# citizen_science_flora.net
KiCad netlist of a schematic drawn in EAGLE
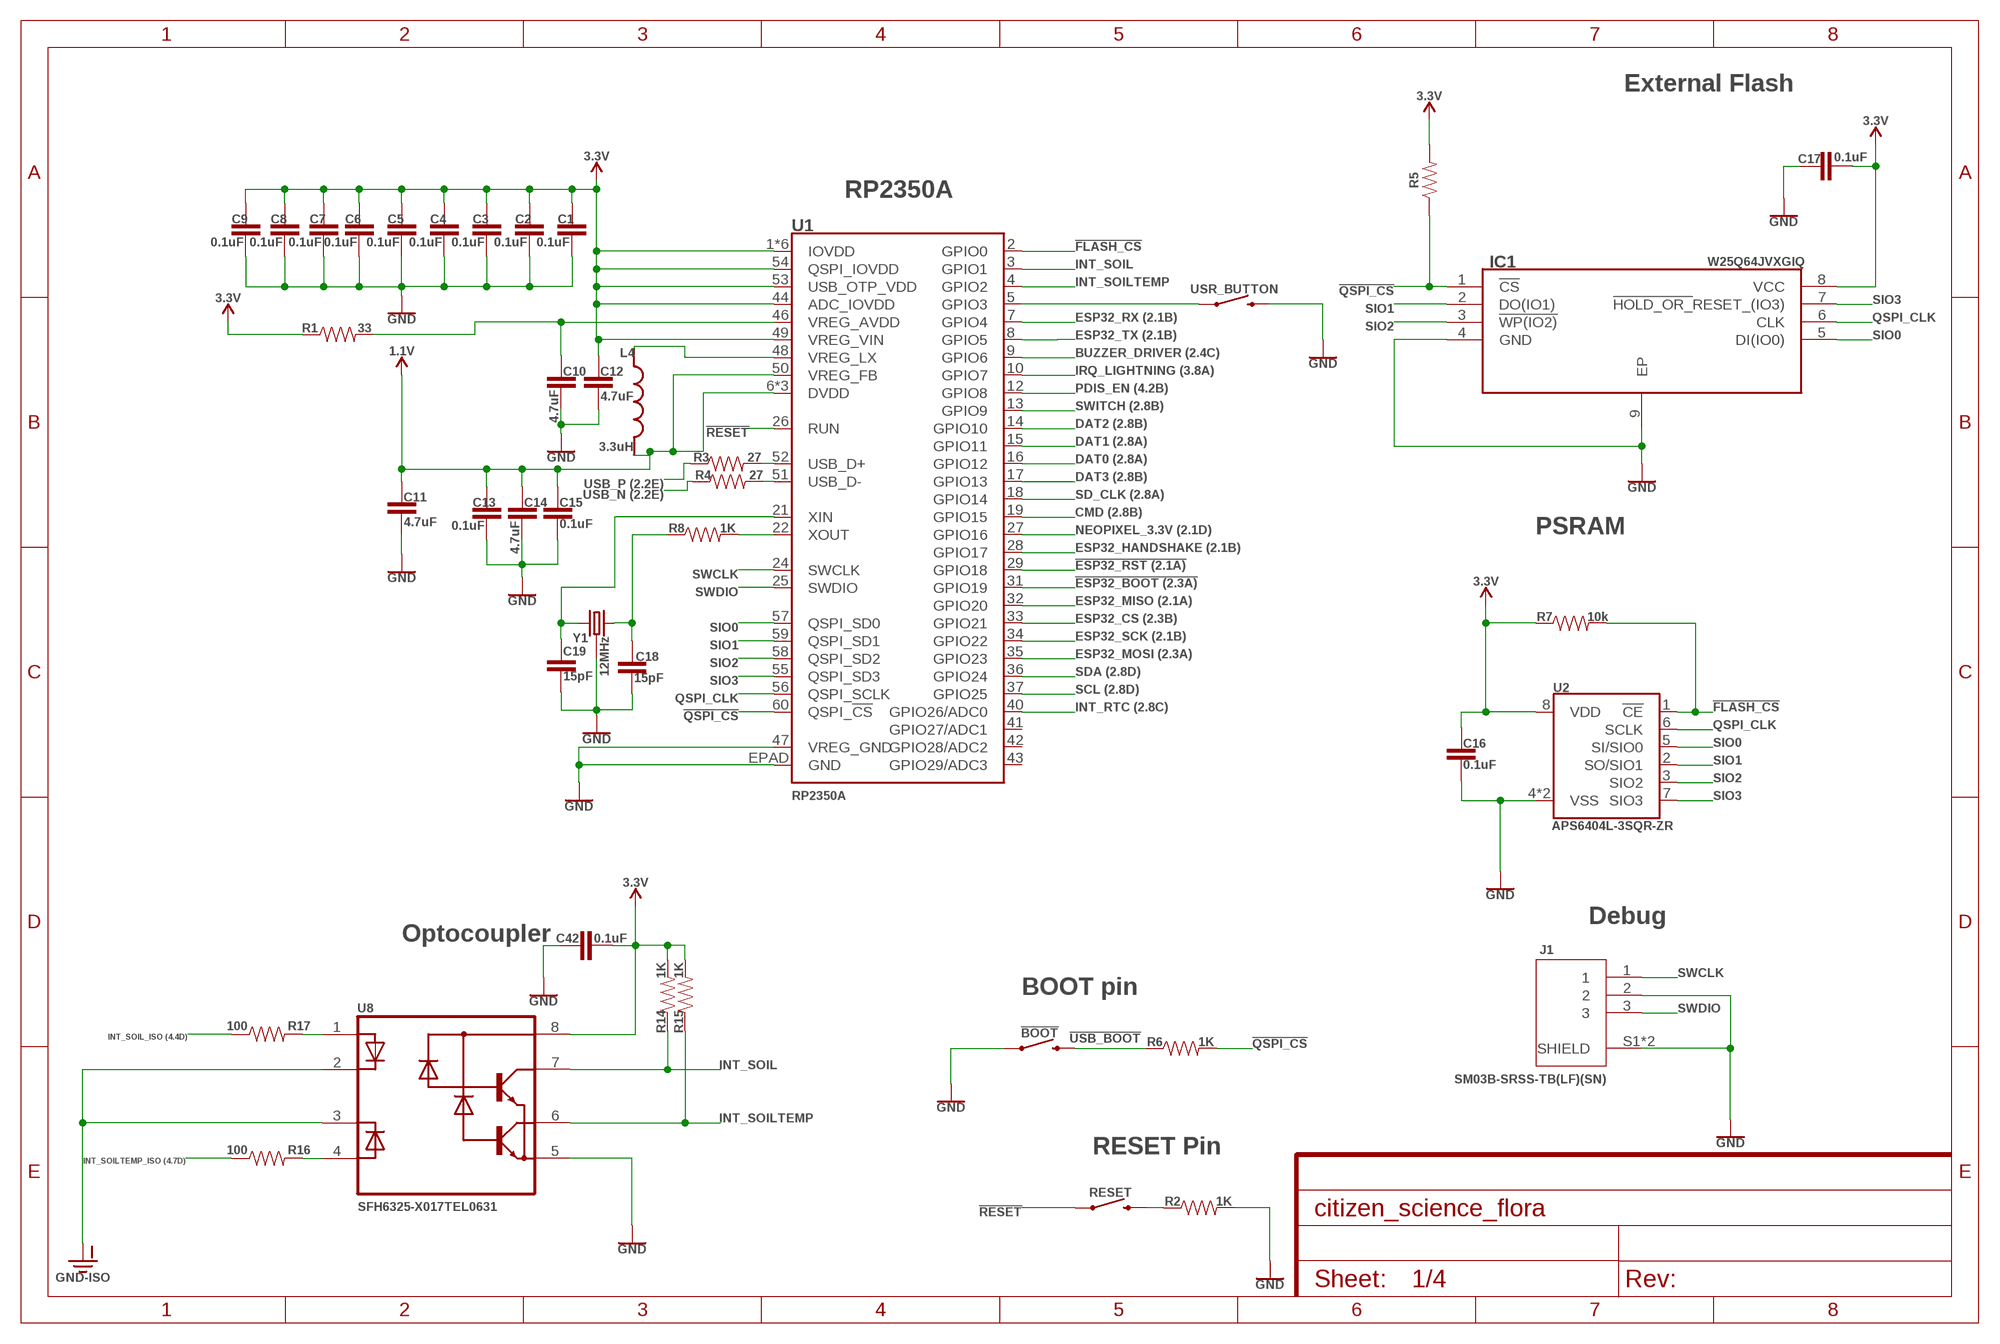
[diagram p0: schematic, sheet 1]
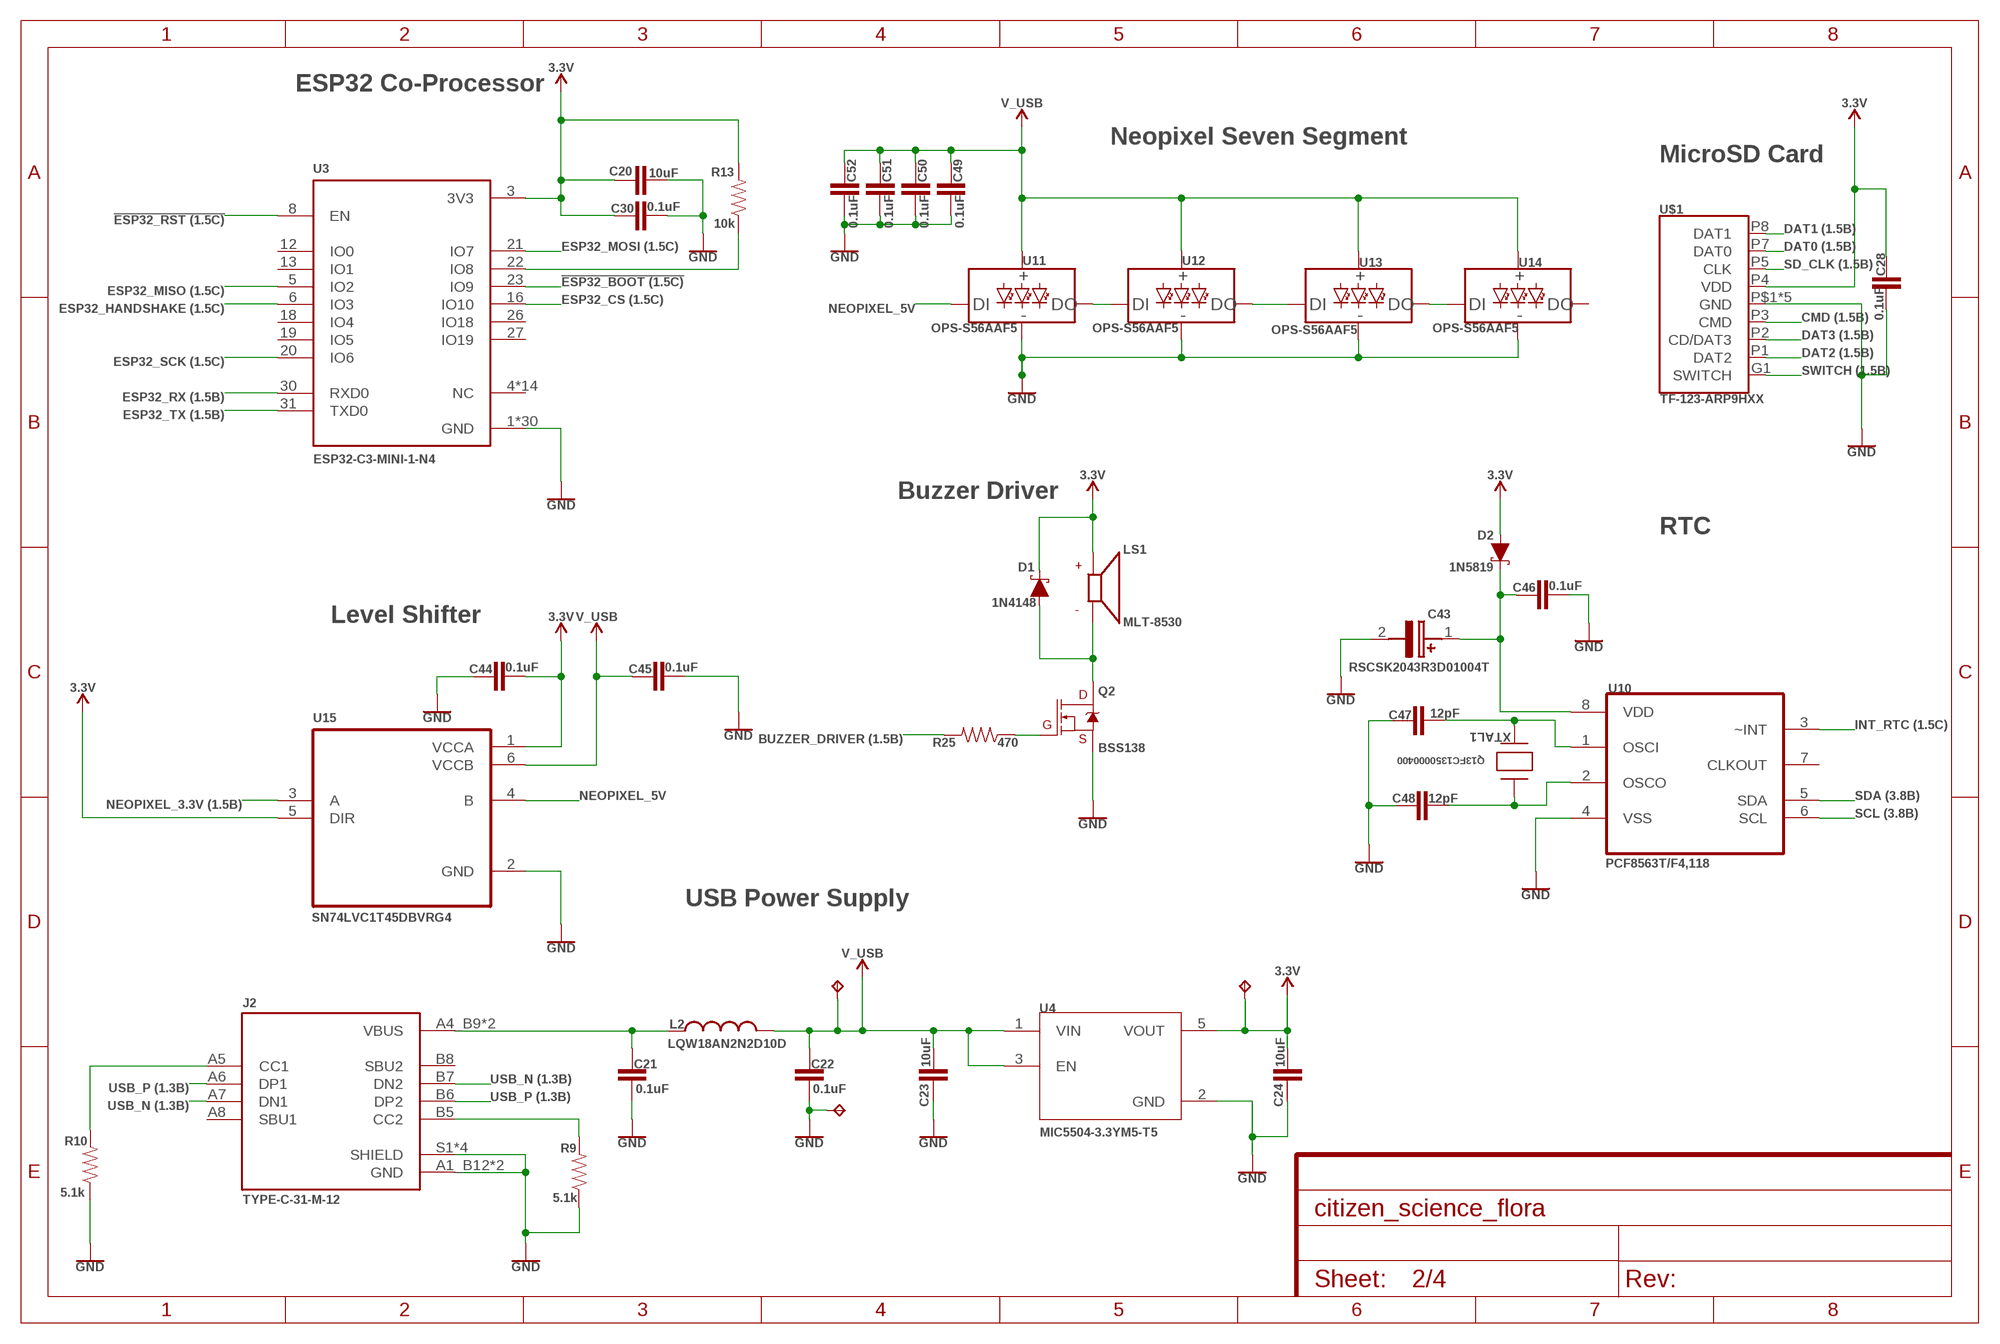
[diagram p1: schematic, sheet 2]
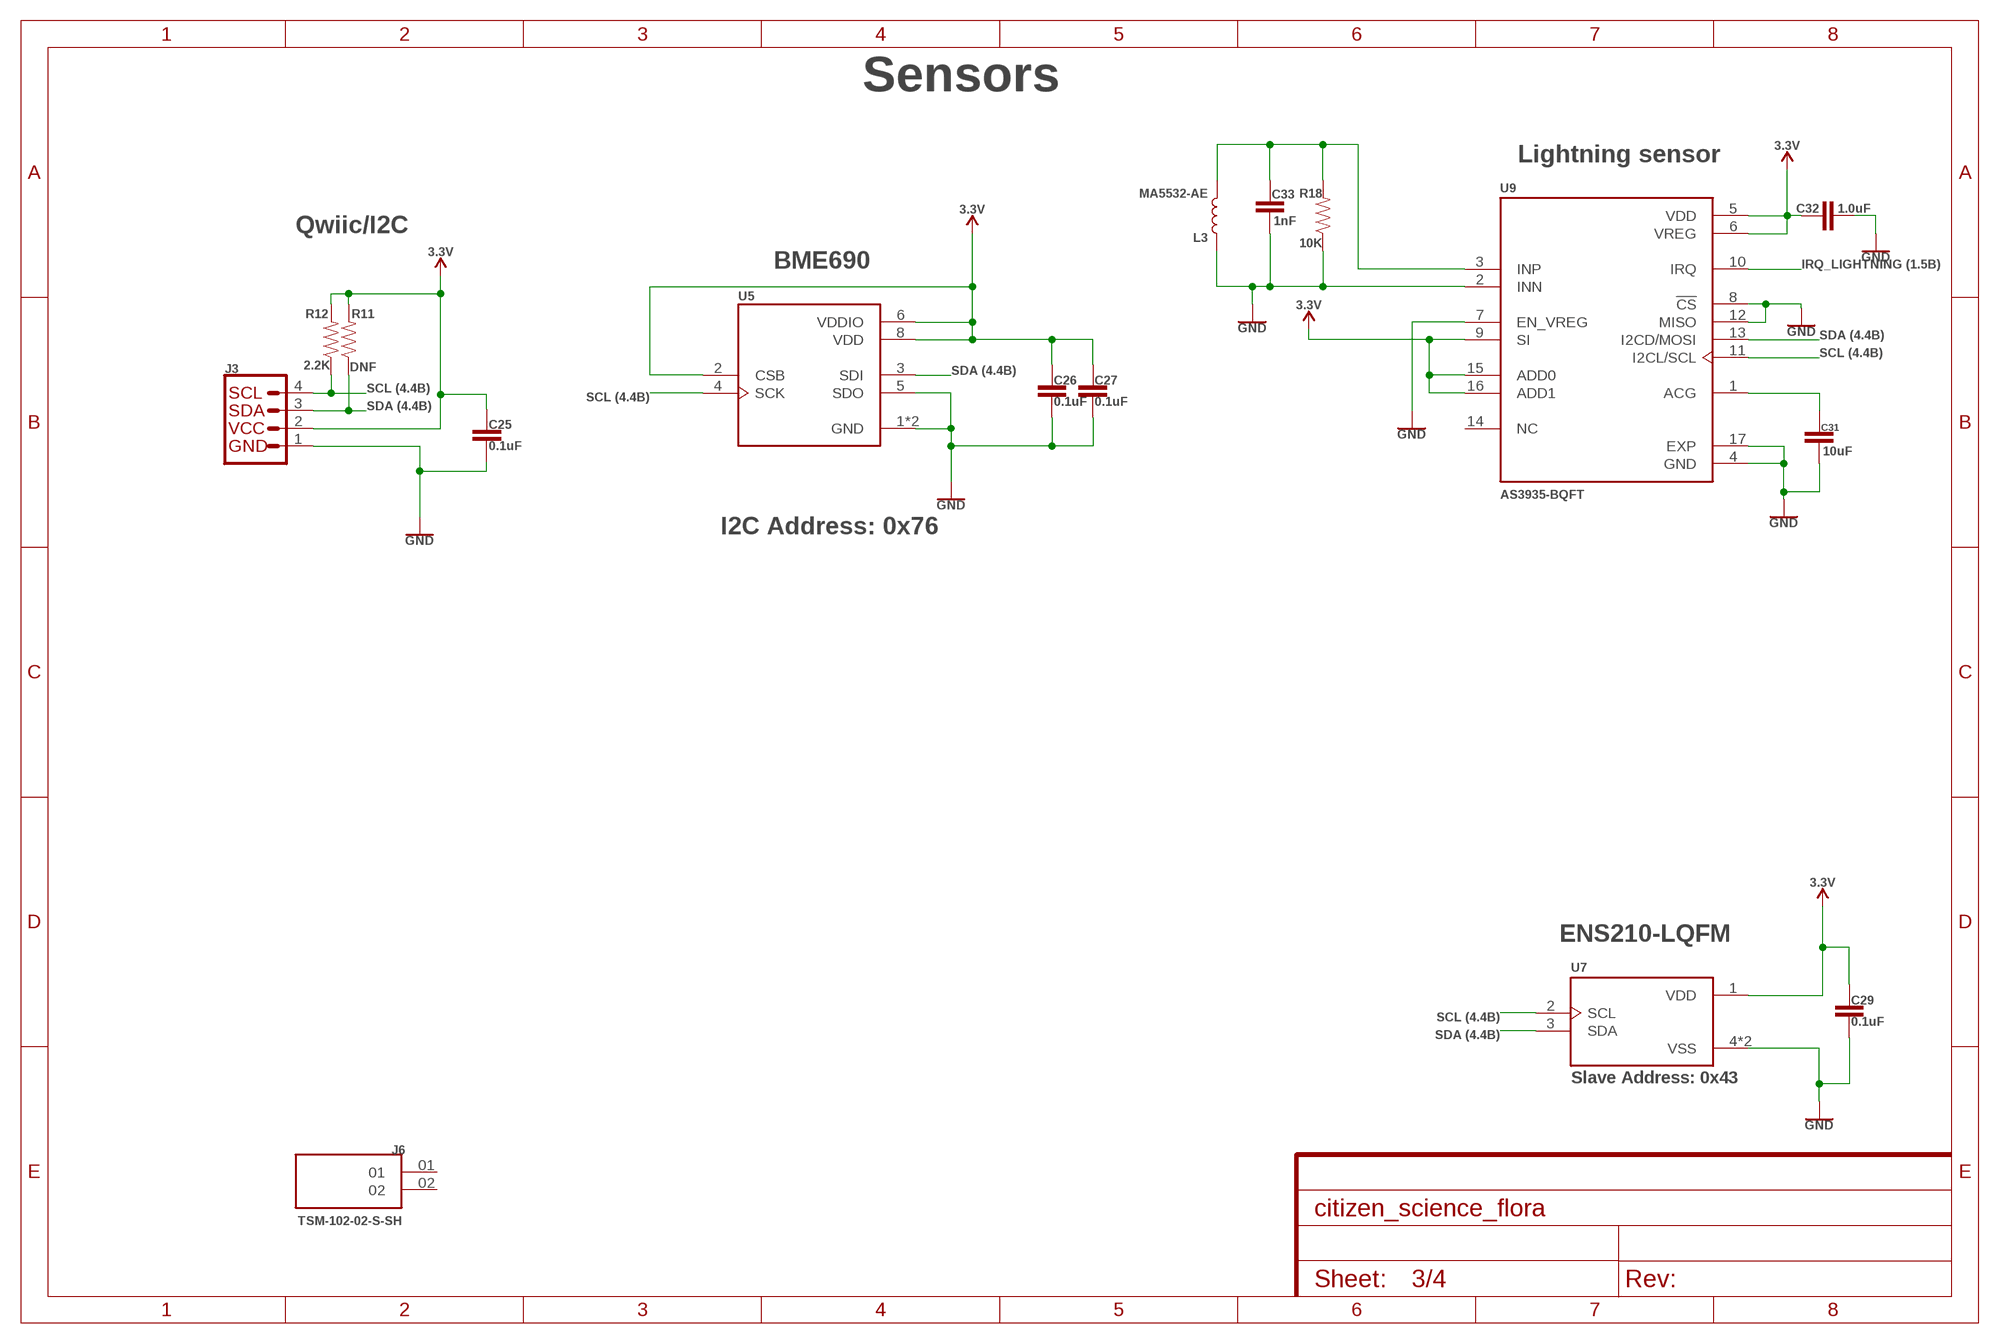
[diagram p2: schematic, sheet 3]
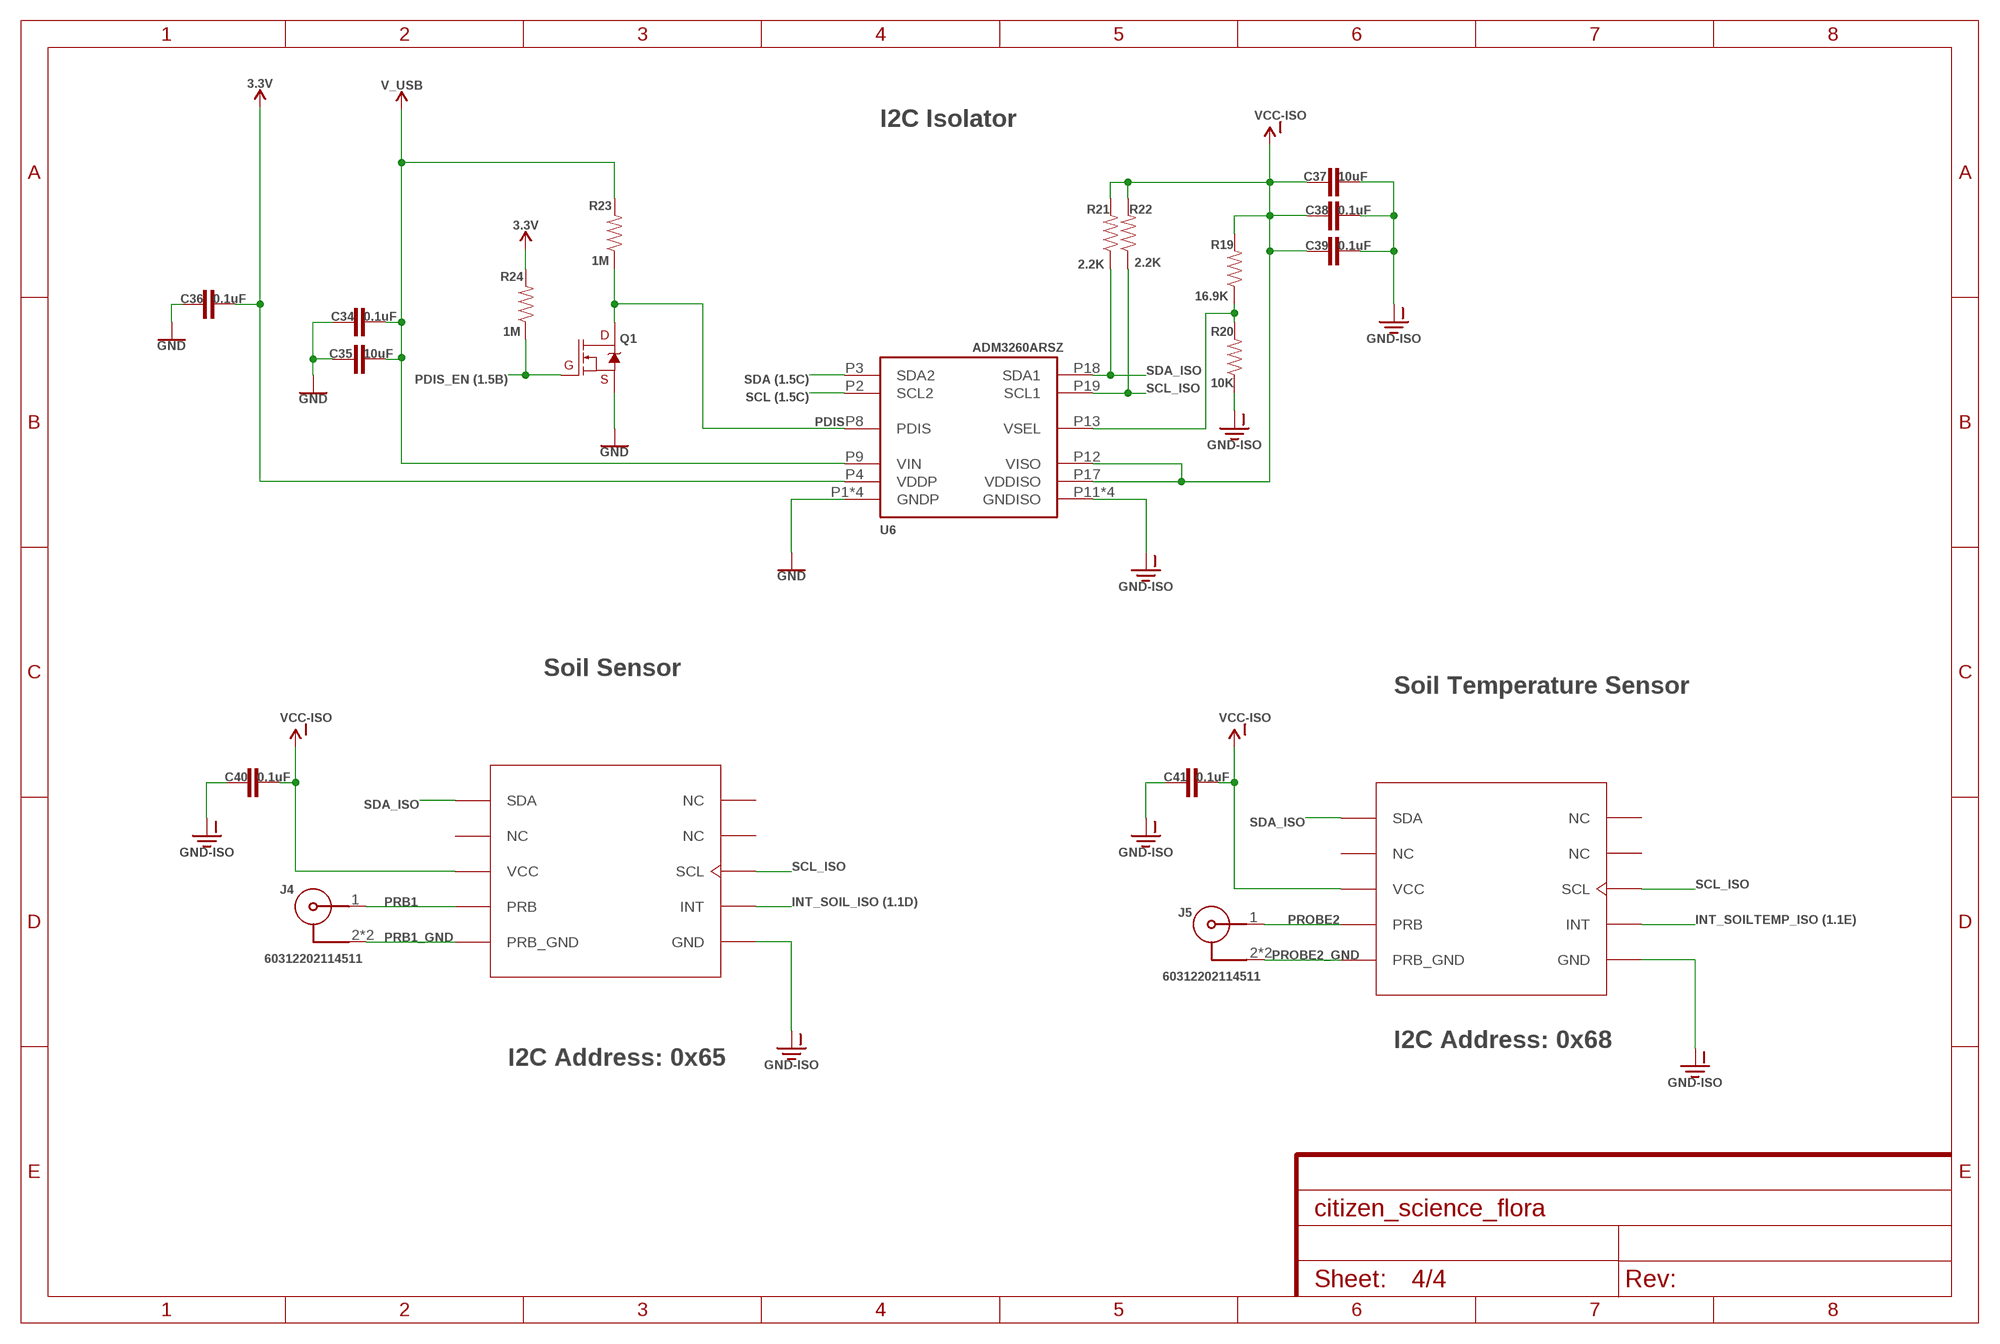
[diagram p3: schematic, sheet 4]

(export (version "E")
  (design (tool "Eeschema 10.0.6"))
  (components
    (comp (ref "3.3V")
      (value "TPB1,27")
      (footprint "eagle-import:B1,27")
      (libsource (lib "eagle-import") (part "TPB1,27"))
    )
    (comp (ref "C20")
      (value "10uF")
      (footprint "eagle-import:0402-TIGHT")
      (libsource (lib "eagle-import") (part "10UF-0402T-6.3V-20%"))
    )
    (comp (ref "C21")
      (value "0.1uF")
      (footprint "eagle-import:0402")
      (libsource (lib "eagle-import") (part "0.1UF-0402-6.3V-10%-X7R"))
    )
    (comp (ref "C22")
      (value "0.1uF")
      (footprint "eagle-import:0402")
      (libsource (lib "eagle-import") (part "0.1UF-0402-6.3V-10%-X7R"))
    )
    (comp (ref "C23")
      (value "10uF")
      (footprint "eagle-import:0402-TIGHT")
      (libsource (lib "eagle-import") (part "10UF-0402T-6.3V-20%"))
    )
    (comp (ref "C24")
      (value "10uF")
      (footprint "eagle-import:0402-TIGHT")
      (libsource (lib "eagle-import") (part "10UF-0402T-6.3V-20%"))
    )
    (comp (ref "C28")
      (value "0.1uF")
      (footprint "eagle-import:0402-TIGHT")
      (libsource (lib "eagle-import") (part "0.1UF-0402T-16V-10%-X7R-WE"))
    )
    (comp (ref "C30")
      (value "0.1uF")
      (footprint "eagle-import:0402")
      (libsource (lib "eagle-import") (part "0.1UF-0402-6.3V-10%-X7R"))
    )
    (comp (ref "C43")
      (value "RSCSK2043R3D01004T")
      (footprint "eagle-import:RSCSK2043R3D01004T")
      (fields (field (name "MOUSER_PART_NUMBER") "555-DSK3R3H204T614H2"))
      (libsource (lib "eagle-import") (part "RSCSK2043R3D01004T"))
    )
    (comp (ref "C44")
      (value "0.1uF")
      (footprint "eagle-import:0402")
      (libsource (lib "eagle-import") (part "0.1UF-0402-6.3V-10%-X7R"))
    )
    (comp (ref "C45")
      (value "0.1uF")
      (footprint "eagle-import:0402")
      (libsource (lib "eagle-import") (part "0.1UF-0402-6.3V-10%-X7R"))
    )
    (comp (ref "C46")
      (value "0.1uF")
      (footprint "eagle-import:0402")
      (libsource (lib "eagle-import") (part "0.1UF-0402-6.3V-10%-X7R"))
    )
    (comp (ref "C47")
      (value "12pF")
      (footprint "eagle-import:0402")
      (libsource (lib "eagle-import") (part "12PF-0402-50V-5%"))
    )
    (comp (ref "C48")
      (value "12pF")
      (footprint "eagle-import:0402")
      (libsource (lib "eagle-import") (part "12PF-0402-50V-5%"))
    )
    (comp (ref "C49")
      (value "0.1uF")
      (footprint "eagle-import:0402")
      (libsource (lib "eagle-import") (part "0.1UF-0402-6.3V-10%-X7R"))
    )
    (comp (ref "C50")
      (value "0.1uF")
      (footprint "eagle-import:0402")
      (libsource (lib "eagle-import") (part "0.1UF-0402-6.3V-10%-X7R"))
    )
    (comp (ref "C51")
      (value "0.1uF")
      (footprint "eagle-import:0402")
      (libsource (lib "eagle-import") (part "0.1UF-0402-6.3V-10%-X7R"))
    )
    (comp (ref "C52")
      (value "0.1uF")
      (footprint "eagle-import:0402")
      (libsource (lib "eagle-import") (part "0.1UF-0402-6.3V-10%-X7R"))
    )
    (comp (ref "D1")
      (value "1N4148")
      (footprint "eagle-import:SOD-323")
      (libsource (lib "eagle-import") (part "DIODE-SCHOTTKY-BAT60A"))
    )
    (comp (ref "D2")
      (value "1N5819")
      (footprint "eagle-import:SOD-323")
      (libsource (lib "eagle-import") (part "DIODE-SCHOTTKY-BAT20J"))
    )
    (comp (ref "GND")
      (value "TPB1,27")
      (footprint "eagle-import:B1,27")
      (libsource (lib "eagle-import") (part "TPB1,27"))
    )
    (comp (ref "J2")
      (value "TYPE-C-31-M-12")
      (footprint "eagle-import:HRO_TYPE-C-31-M-12")
      (fields (field (name "MF") "HRO Electronics Co., Ltd."))
      (libsource (lib "eagle-import") (part "TYPE-C-31-M-12"))
    )
    (comp (ref "L2")
      (value "LQW18AN2N2D10D")
      (footprint "eagle-import:INDC1608X100N")
      (fields (field (name "MF") "Murata"))
      (libsource (lib "eagle-import") (part "LQW18AN2N2D10D"))
    )
    (comp (ref "LS1")
      (value "MLT-8530")
      (footprint "eagle-import:XDCR_CMT-8504-100-SMT-TR")
      (fields (field (name "MANUFACTURER") "CUI Inc."))
      (libsource (lib "eagle-import") (part "CMT-8504-100-SMT-TR"))
    )
    (comp (ref "Q2")
      (value "BSS138")
      (footprint "eagle-import:SOT323")
      (libsource (lib "eagle-import") (part "MOSFET-NCH-2N7002PW"))
    )
    (comp (ref "R9")
      (value "5.1k")
      (footprint "eagle-import:0402")
      (libsource (lib "eagle-import") (part "5.1KOHM-0402-1/16W-1%"))
    )
    (comp (ref "R10")
      (value "5.1k")
      (footprint "eagle-import:0402")
      (libsource (lib "eagle-import") (part "5.1KOHM-0402-1/16W-1%"))
    )
    (comp (ref "R13")
      (value "10k")
      (footprint "eagle-import:0402")
      (libsource (lib "eagle-import") (part "10KOHM-0402-1/16W-1%"))
    )
    (comp (ref "R25")
      (value "470")
      (footprint "eagle-import:0402")
      (libsource (lib "eagle-import") (part "10KOHM-0402-1/16W-1%"))
    )
    (comp (ref "U$1")
      (value "TF-123-ARP9HXX")
      (footprint "eagle-import:MICROSDCARD")
      (libsource (lib "eagle-import") (part "TF-123-ARP9HXX"))
    )
    (comp (ref "U3")
      (value "ESP32-C3-MINI-1-N4")
      (footprint "eagle-import:XCVR_ESP32-C3-MINI-1-N4")
      (fields (field (name "MF") "Espressif Systems"))
      (libsource (lib "eagle-import") (part "ESP32-C3-MINI-1-N4"))
    )
    (comp (ref "U4")
      (value "MIC5504-3.3YM5-T5")
      (footprint "eagle-import:SOT95P280X145-5N")
      (fields (field (name "MF") "Microchip"))
      (libsource (lib "eagle-import") (part "MIC5504-3.3YM5-T5"))
    )
    (comp (ref "U10")
      (value "PCF8563T/F4,118")
      (footprint "eagle-import:SOIC127P600X175-8N")
      (fields (field (name "MF") "NXP USA"))
      (libsource (lib "eagle-import") (part "PCF8563T/F4,118"))
    )
    (comp (ref "U11")
      (value "OPS-S56AAF5")
      (footprint "eagle-import:OPS-S56AAF5")
      (libsource (lib "eagle-import") (part "OPS-S56AAF5"))
    )
    (comp (ref "U12")
      (value "OPS-S56AAF5")
      (footprint "eagle-import:OPS-S56AAF5")
      (libsource (lib "eagle-import") (part "OPS-S56AAF5"))
    )
    (comp (ref "U13")
      (value "OPS-S56AAF5")
      (footprint "eagle-import:OPS-S56AAF5")
      (libsource (lib "eagle-import") (part "OPS-S56AAF5"))
    )
    (comp (ref "U14")
      (value "OPS-S56AAF5")
      (footprint "eagle-import:OPS-S56AAF5")
      (libsource (lib "eagle-import") (part "OPS-S56AAF5"))
    )
    (comp (ref "U15")
      (value "SN74LVC1T45DBVRG4")
      (footprint "eagle-import:SOT95P280X145-6N")
      (fields (field (name "MF") "Texas Instruments"))
      (libsource (lib "eagle-import") (part "SN74LVC1T45DBVRG4"))
    )
    (comp (ref "USB")
      (value "V_USB")
      (footprint "eagle-import:B1,27")
      (libsource (lib "eagle-import") (part "TPB1,27"))
    )
    (comp (ref "XTAL1")
      (value "Q13FC1350000400")
      (footprint "eagle-import:XTAL_FC-135_EPS")
      (fields (field (name "MF") "EPSON"))
      (libsource (lib "eagle-import") (part "Q13FC1350000400"))
    )
    (comp (ref "C25")
      (value "0.1uF")
      (footprint "eagle-import:0402-TIGHT")
      (libsource (lib "eagle-import") (part "0.1UF-0402T-16V-10%-X7R-WE"))
    )
    (comp (ref "C26")
      (value "0.1uF")
      (footprint "eagle-import:0402-TIGHT")
      (libsource (lib "eagle-import") (part "0.1UF-0402T-16V-10%-X7R-WE"))
    )
    (comp (ref "C27")
      (value "0.1uF")
      (footprint "eagle-import:0402-TIGHT")
      (libsource (lib "eagle-import") (part "0.1UF-0402T-16V-10%-X7R-WE"))
    )
    (comp (ref "C29")
      (value "0.1uF")
      (footprint "eagle-import:0402-TIGHT")
      (libsource (lib "eagle-import") (part "0.1UF-0402T-16V-10%-X7R-WE"))
    )
    (comp (ref "C31")
      (value "10uF")
      (footprint "eagle-import:0402-TIGHT")
      (libsource (lib "eagle-import") (part "10UF-0402T-6.3V-20%"))
    )
    (comp (ref "C32")
      (value "1.0uF")
      (footprint "eagle-import:0402")
      (libsource (lib "eagle-import") (part "1.0UF-0402-16V-10%"))
    )
    (comp (ref "C33")
      (value "1nF")
      (footprint "eagle-import:0402")
      (libsource (lib "eagle-import") (part "1.0NF/1000PF-0402-25V-10%-X7R"))
    )
    (comp (ref "J3")
      (value "QWIIC_CONNECTORJS-1MM")
      (footprint "eagle-import:1X04_1MM_RA")
      (libsource (lib "eagle-import") (part "QWIIC_CONNECTORJS-1MM"))
    )
    (comp (ref "J6")
      (value "TSM-102-02-S-SH")
      (footprint "eagle-import:SAMTEC_TSM-102-02-S-SH")
      (fields (field (name "MF") "Samtec"))
      (libsource (lib "eagle-import") (part "TSM-102-02-S-SH"))
    )
    (comp (ref "L3")
      (value "MA5532-AE")
      (footprint "eagle-import:MA5532-AE")
      (fields (field (name "MF") "Coilcraft"))
      (libsource (lib "eagle-import") (part "MA5532-AE"))
    )
    (comp (ref "R11")
      (value "DNF")
      (footprint "eagle-import:0402")
      (libsource (lib "eagle-import") (part "2.2KOHM-0402-1/16W-1%"))
    )
    (comp (ref "R12")
      (value "2.2K")
      (footprint "eagle-import:0402")
      (libsource (lib "eagle-import") (part "2.2KOHM-0402-1/16W-1%"))
    )
    (comp (ref "R18")
      (value "10K")
      (footprint "eagle-import:0402-TIGHT")
      (libsource (lib "eagle-import") (part "10KOHM-0402-1/10W-0.1%"))
    )
    (comp (ref "U5")
      (value "BME690")
      (footprint "eagle-import:IC_BME688")
      (fields (field (name "MF") "Bosch Sensortec") (field (name "MP") "BME688"))
      (libsource (lib "eagle-import") (part "BME690"))
    )
    (comp (ref "U7")
      (value "ENS210-LQFM")
      (footprint "eagle-import:XDCR_ENS210-LQFM")
      (fields (field (name "MF") "ScioSense"))
      (libsource (lib "eagle-import") (part "ENS210-LQFM"))
    )
    (comp (ref "U9")
      (value "AS3935-BQFT")
      (footprint "eagle-import:QFN65P400X400X80-17N")
      (fields (field (name "MF") "ScioSense"))
      (libsource (lib "eagle-import") (part "AS3935-BQFT"))
    )
    (comp (ref "C34")
      (value "0.1uF")
      (footprint "eagle-import:0402-TIGHT")
      (libsource (lib "eagle-import") (part "0.1UF-0402T-16V-10%-X7R-WE"))
    )
    (comp (ref "C35")
      (value "10uF")
      (footprint "eagle-import:0402-TIGHT")
      (libsource (lib "eagle-import") (part "10UF-0402T-6.3V-20%"))
    )
    (comp (ref "C36")
      (value "0.1uF")
      (footprint "eagle-import:0402-TIGHT")
      (libsource (lib "eagle-import") (part "0.1UF-0402T-16V-10%-X7R-WE"))
    )
    (comp (ref "C37")
      (value "10uF")
      (footprint "eagle-import:0402-TIGHT")
      (libsource (lib "eagle-import") (part "10UF-0402T-6.3V-20%"))
    )
    (comp (ref "C38")
      (value "0.1uF")
      (footprint "eagle-import:0402-TIGHT")
      (libsource (lib "eagle-import") (part "0.1UF-0402T-16V-10%-X7R-WE"))
    )
    (comp (ref "C39")
      (value "0.1uF")
      (footprint "eagle-import:0402-TIGHT")
      (libsource (lib "eagle-import") (part "0.1UF-0402T-16V-10%-X7R-WE"))
    )
    (comp (ref "C40")
      (value "0.1uF")
      (footprint "eagle-import:0402-TIGHT")
      (libsource (lib "eagle-import") (part "0.1UF-0402T-16V-10%-X7R-WE"))
    )
    (comp (ref "C41")
      (value "0.1uF")
      (footprint "eagle-import:0402-TIGHT")
      (libsource (lib "eagle-import") (part "0.1UF-0402T-16V-10%-X7R-WE"))
    )
    (comp (ref "J4")
      (value "60312202114511")
      (footprint "eagle-import:60312202114511")
      (fields (field (name "MF") "Wurth Electronics"))
      (libsource (lib "eagle-import") (part "60312202114511"))
    )
    (comp (ref "J5")
      (value "60312202114511")
      (footprint "eagle-import:60312202114511")
      (fields (field (name "MF") "Wurth Electronics"))
      (libsource (lib "eagle-import") (part "60312202114511"))
    )
    (comp (ref "Q1")
      (value "220mA/50V/3.5Ω")
      (footprint "eagle-import:SOT23-3")
      (libsource (lib "eagle-import") (part "MOSFET-NCH-BSS138"))
    )
    (comp (ref "R19")
      (value "16.9K")
      (footprint "eagle-import:0402")
      (libsource (lib "eagle-import") (part "RESISTOR0402"))
    )
    (comp (ref "R20")
      (value "10K")
      (footprint "eagle-import:0402-TIGHT")
      (libsource (lib "eagle-import") (part "10KOHM-0402-1/10W-0.1%"))
    )
    (comp (ref "R21")
      (value "2.2K")
      (footprint "eagle-import:0402")
      (libsource (lib "eagle-import") (part "2.2KOHM-0402-1/16W-1%"))
    )
    (comp (ref "R22")
      (value "2.2K")
      (footprint "eagle-import:0402")
      (libsource (lib "eagle-import") (part "2.2KOHM-0402-1/16W-1%"))
    )
    (comp (ref "R23")
      (value "1M")
      (footprint "eagle-import:0402")
      (libsource (lib "eagle-import") (part "1MOHM-0402-1/16W-5%"))
    )
    (comp (ref "R24")
      (value "1M")
      (footprint "eagle-import:0402")
      (libsource (lib "eagle-import") (part "1MOHM-0402-1/16W-5%"))
    )
    (comp (ref "U$2")
      (value "PH-OEM")
      (footprint "eagle-import:PH_SENSOR")
      (libsource (lib "eagle-import") (part "PH-OEM"))
    )
    (comp (ref "U$3")
      (value "PH-OEM")
      (footprint "eagle-import:PH_SENSOR")
      (libsource (lib "eagle-import") (part "PH-OEM"))
    )
    (comp (ref "U6")
      (value "ADM3260ARSZ")
      (footprint "eagle-import:SSOP20")
      (fields (field (name "MF") "Analog Devices"))
      (libsource (lib "eagle-import") (part "ADM3260ARSZ"))
    )
    (comp (ref "!BOOT")
      (value "MOMENTARY-SWITCH-SPST-SMD-4.6X2.8MM")
      (footprint "eagle-import:TACTILE_SWITCH_SMD_4.6X2.8MM")
      (libsource (lib "eagle-import") (part "MOMENTARY-SWITCH-SPST-SMD-4.6X2.8MM"))
    )
    (comp (ref "C1")
      (value "0.1uF")
      (footprint "eagle-import:0402-TIGHT")
      (libsource (lib "eagle-import") (part "0.1UF-0402T-16V-10%-X7R-WE"))
    )
    (comp (ref "C2")
      (value "0.1uF")
      (footprint "eagle-import:0402-TIGHT")
      (libsource (lib "eagle-import") (part "0.1UF-0402T-16V-10%-X7R-WE"))
    )
    (comp (ref "C3")
      (value "0.1uF")
      (footprint "eagle-import:0402-TIGHT")
      (libsource (lib "eagle-import") (part "0.1UF-0402T-16V-10%-X7R-WE"))
    )
    (comp (ref "C4")
      (value "0.1uF")
      (footprint "eagle-import:0402-TIGHT")
      (libsource (lib "eagle-import") (part "0.1UF-0402T-16V-10%-X7R-WE"))
    )
    (comp (ref "C5")
      (value "0.1uF")
      (footprint "eagle-import:0402-TIGHT")
      (libsource (lib "eagle-import") (part "0.1UF-0402T-16V-10%-X7R-WE"))
    )
    (comp (ref "C6")
      (value "0.1uF")
      (footprint "eagle-import:0402-TIGHT")
      (libsource (lib "eagle-import") (part "0.1UF-0402T-16V-10%-X7R-WE"))
    )
    (comp (ref "C7")
      (value "0.1uF")
      (footprint "eagle-import:0402-TIGHT")
      (libsource (lib "eagle-import") (part "0.1UF-0402T-16V-10%-X7R-WE"))
    )
    (comp (ref "C8")
      (value "0.1uF")
      (footprint "eagle-import:0402-TIGHT")
      (libsource (lib "eagle-import") (part "0.1UF-0402T-16V-10%-X7R-WE"))
    )
    (comp (ref "C9")
      (value "0.1uF")
      (footprint "eagle-import:0402-TIGHT")
      (libsource (lib "eagle-import") (part "0.1UF-0402T-16V-10%-X7R-WE"))
    )
    (comp (ref "C10")
      (value "4.7uF")
      (footprint "eagle-import:0402-TIGHT")
      (libsource (lib "eagle-import") (part "4.7UF-0402_TIGHT-6.3V-20%-X5R"))
    )
    (comp (ref "C11")
      (value "4.7uF")
      (footprint "eagle-import:0402-TIGHT")
      (libsource (lib "eagle-import") (part "4.7UF-0402_TIGHT-6.3V-20%-X5R"))
    )
    (comp (ref "C12")
      (value "4.7uF")
      (footprint "eagle-import:0402-TIGHT")
      (libsource (lib "eagle-import") (part "4.7UF-0402_TIGHT-6.3V-20%-X5R"))
    )
    (comp (ref "C13")
      (value "0.1uF")
      (footprint "eagle-import:0402-TIGHT")
      (libsource (lib "eagle-import") (part "0.1UF-0402T-16V-10%-X7R-WE"))
    )
    (comp (ref "C14")
      (value "4.7uF")
      (footprint "eagle-import:0402-TIGHT")
      (libsource (lib "eagle-import") (part "4.7UF-0402_TIGHT-6.3V-20%-X5R"))
    )
    (comp (ref "C15")
      (value "0.1uF")
      (footprint "eagle-import:0402-TIGHT")
      (libsource (lib "eagle-import") (part "0.1UF-0402T-16V-10%-X7R-WE"))
    )
    (comp (ref "C16")
      (value "0.1uF")
      (footprint "eagle-import:0402-TIGHT")
      (libsource (lib "eagle-import") (part "0.1UF-0402T-16V-10%-X7R-WE"))
    )
    (comp (ref "C17")
      (value "0.1uF")
      (footprint "eagle-import:0402-TIGHT")
      (libsource (lib "eagle-import") (part "0.1UF-0402T-16V-10%-X7R-WE"))
    )
    (comp (ref "C18")
      (value "15pF")
      (footprint "eagle-import:0402")
      (libsource (lib "eagle-import") (part "15PF-0402-50V-5%"))
    )
    (comp (ref "C19")
      (value "15pF")
      (footprint "eagle-import:0402")
      (libsource (lib "eagle-import") (part "15PF-0402-50V-5%"))
    )
    (comp (ref "C42")
      (value "0.1uF")
      (footprint "eagle-import:0402-TIGHT")
      (libsource (lib "eagle-import") (part "0.1UF-0402T-16V-10%-X7R-WE"))
    )
    (comp (ref "IC1")
      (value "W25Q64JVXGIQ")
      (footprint "eagle-import:SON80P400X400X50-9N")
      (libsource (lib "eagle-import") (part "W25Q64JVXGIQ"))
    )
    (comp (ref "J1")
      (value "SM03B-SRSS-TB(LF)(SN)")
      (footprint "eagle-import:JST_SM03B-SRSS-TB(LF)(SN)")
      (fields (field (name "MF") "JST Sales America Inc."))
      (libsource (lib "eagle-import") (part "SM03B-SRSS-TB(LF)(SN)"))
    )
    (comp (ref "L4")
      (value "3.3uH")
      (footprint "eagle-import:IND_LQH2MCN120K02L")
      (fields (field (name "MF") "Murata") (field (name "MP") "LQH2MCN120K02L"))
      (libsource (lib "eagle-import") (part "LQH2MCN120K02L"))
    )
    (comp (ref "R1")
      (value "33")
      (footprint "eagle-import:0402")
      (libsource (lib "eagle-import") (part "33OHM-0402-1/10W-1%"))
    )
    (comp (ref "R2")
      (value "1K")
      (footprint "eagle-import:0402")
      (libsource (lib "eagle-import") (part "1KOHM-0402-1/16W-1%"))
    )
    (comp (ref "R3")
      (value "27")
      (footprint "eagle-import:0402-TIGHT")
      (libsource (lib "eagle-import") (part "27OHM"))
    )
    (comp (ref "R4")
      (value "27")
      (footprint "eagle-import:0402-TIGHT")
      (libsource (lib "eagle-import") (part "27OHM"))
    )
    (comp (ref "R5")
      (value "RESISTOR0402")
      (footprint "eagle-import:0402")
      (libsource (lib "eagle-import") (part "RESISTOR0402"))
    )
    (comp (ref "R6")
      (value "1K")
      (footprint "eagle-import:0402")
      (libsource (lib "eagle-import") (part "1KOHM-0402-1/16W-1%"))
    )
    (comp (ref "R7")
      (value "10k")
      (footprint "eagle-import:0402")
      (libsource (lib "eagle-import") (part "10KOHM-0402-1/16W-1%"))
    )
    (comp (ref "R8")
      (value "1K")
      (footprint "eagle-import:0402")
      (libsource (lib "eagle-import") (part "1KOHM-0402-1/16W-1%"))
    )
    (comp (ref "R14")
      (value "1K")
      (footprint "eagle-import:0402")
      (libsource (lib "eagle-import") (part "1KOHM-0402-1/16W-1%"))
    )
    (comp (ref "R15")
      (value "1K")
      (footprint "eagle-import:0402")
      (libsource (lib "eagle-import") (part "1KOHM-0402-1/16W-1%"))
    )
    (comp (ref "R16")
      (value "100")
      (footprint "eagle-import:0402-TIGHT")
      (libsource (lib "eagle-import") (part "100OHM-0402-TIGHT-1/16W-1%"))
    )
    (comp (ref "R17")
      (value "100")
      (footprint "eagle-import:0402-TIGHT")
      (libsource (lib "eagle-import") (part "100OHM-0402-TIGHT-1/16W-1%"))
    )
    (comp (ref "RESET")
      (value "MOMENTARY-SWITCH-SPST-SMD-4.6X2.8MM")
      (footprint "eagle-import:TACTILE_SWITCH_SMD_4.6X2.8MM")
      (libsource (lib "eagle-import") (part "MOMENTARY-SWITCH-SPST-SMD-4.6X2.8MM"))
    )
    (comp (ref "U1")
      (value "RP2350A")
      (footprint "eagle-import:RP2350A")
      (libsource (lib "eagle-import") (part "RP2350A"))
    )
    (comp (ref "U2")
      (value "APS6404L-3SQR-ZR")
      (footprint "eagle-import:APS6404L-3SQR-ZR")
      (libsource (lib "eagle-import") (part "APS6404L-3SQR-ZR"))
    )
    (comp (ref "U8")
      (value "SFH6325-X017TEL0631")
      (footprint "eagle-import:SOIC127P599X175-8N")
      (libsource (lib "eagle-import") (part "SFH6325-X017TEL0631"))
    )
    (comp (ref "USR_BUTTON")
      (value "MOMENTARY-SWITCH-SPST-SMD-4.6X2.8MM")
      (footprint "eagle-import:TACTILE_SWITCH_SMD_4.6X2.8MM")
      (libsource (lib "eagle-import") (part "MOMENTARY-SWITCH-SPST-SMD-4.6X2.8MM"))
    )
    (comp (ref "Y1")
      (value "12MHz")
      (footprint "eagle-import:CRYSTAL-SMD-3.2X2.5MM")
      (libsource (lib "eagle-import") (part "CRYSTAL-GROUNDEDSMD-3.2X2.5"))
    )
  )
  (nets
    (net (code "1") (name "1.1V") (class "Default")
      (node (ref "C11") (pin "1") (pinfunction "1_1") (pintype "passive"))
      (node (ref "C13") (pin "1") (pinfunction "1_1") (pintype "passive"))
      (node (ref "C14") (pin "1") (pinfunction "1_1") (pintype "passive"))
      (node (ref "C15") (pin "1") (pinfunction "1_1") (pintype "passive"))
      (node (ref "L4") (pin "2") (pinfunction "P$2_2") (pintype "bidirectional"))
      (node (ref "U1") (pin "23") (pinfunction "DVDD_23") (pintype "bidirectional"))
      (node (ref "U1") (pin "39") (pinfunction "DVDD_39") (pintype "bidirectional"))
      (node (ref "U1") (pin "50") (pinfunction "VREG_FB_50") (pintype "bidirectional"))
      (node (ref "U1") (pin "6") (pinfunction "DVDD_6") (pintype "bidirectional"))
    )
    (net (code "2") (name "3.3V") (class "Default")
      (node (ref "3.3V") (pin "TP") (pinfunction "TP_TP") (pintype "input"))
      (node (ref "C1") (pin "1") (pinfunction "1_1") (pintype "passive"))
      (node (ref "C12") (pin "1") (pinfunction "1_1") (pintype "passive"))
      (node (ref "C16") (pin "1") (pinfunction "1_1") (pintype "passive"))
      (node (ref "C17") (pin "2") (pinfunction "2_2") (pintype "passive"))
      (node (ref "C2") (pin "1") (pinfunction "1_1") (pintype "passive"))
      (node (ref "C20") (pin "1") (pinfunction "1_1") (pintype "passive"))
      (node (ref "C24") (pin "2") (pinfunction "2_2") (pintype "passive"))
      (node (ref "C25") (pin "1") (pinfunction "1_1") (pintype "passive"))
      (node (ref "C26") (pin "1") (pinfunction "1_1") (pintype "passive"))
      (node (ref "C27") (pin "1") (pinfunction "1_1") (pintype "passive"))
      (node (ref "C28") (pin "1") (pinfunction "1_1") (pintype "passive"))
      (node (ref "C29") (pin "1") (pinfunction "1_1") (pintype "passive"))
      (node (ref "C3") (pin "1") (pinfunction "1_1") (pintype "passive"))
      (node (ref "C30") (pin "1") (pinfunction "1_1") (pintype "passive"))
      (node (ref "C32") (pin "1") (pinfunction "1_1") (pintype "passive"))
      (node (ref "C36") (pin "2") (pinfunction "2_2") (pintype "passive"))
      (node (ref "C4") (pin "1") (pinfunction "1_1") (pintype "passive"))
      (node (ref "C42") (pin "2") (pinfunction "2_2") (pintype "passive"))
      (node (ref "C44") (pin "2") (pinfunction "2_2") (pintype "passive"))
      (node (ref "C5") (pin "1") (pinfunction "1_1") (pintype "passive"))
      (node (ref "C6") (pin "1") (pinfunction "1_1") (pintype "passive"))
      (node (ref "C7") (pin "1") (pinfunction "1_1") (pintype "passive"))
      (node (ref "C8") (pin "1") (pinfunction "1_1") (pintype "passive"))
      (node (ref "C9") (pin "1") (pinfunction "1_1") (pintype "passive"))
      (node (ref "D1") (pin "C") (pinfunction "C_C") (pintype "passive"))
      (node (ref "D2") (pin "A") (pinfunction "A_A") (pintype "passive"))
      (node (ref "IC1") (pin "8") (pinfunction "VCC_8") (pintype "bidirectional"))
      (node (ref "J3") (pin "2") (pinfunction "2_2") (pintype "power_in"))
      (node (ref "LS1") (pin "P") (pinfunction "P_P") (pintype "passive"))
      (node (ref "R1") (pin "1") (pinfunction "1_1") (pintype "passive"))
      (node (ref "R11") (pin "2") (pinfunction "2_2") (pintype "passive"))
      (node (ref "R12") (pin "2") (pinfunction "2_2") (pintype "passive"))
      (node (ref "R13") (pin "2") (pinfunction "2_2") (pintype "passive"))
      (node (ref "R14") (pin "2") (pinfunction "2_2") (pintype "passive"))
      (node (ref "R15") (pin "2") (pinfunction "2_2") (pintype "passive"))
      (node (ref "R24") (pin "2") (pinfunction "2_2") (pintype "passive"))
      (node (ref "R5") (pin "2") (pinfunction "2_2") (pintype "passive"))
      (node (ref "R7") (pin "1") (pinfunction "1_1") (pintype "passive"))
      (node (ref "U$1") (pin "P4") (pinfunction "VDD_P4") (pintype "power_in"))
      (node (ref "U1") (pin "1") (pinfunction "IOVDD_1") (pintype "bidirectional"))
      (node (ref "U1") (pin "11") (pinfunction "IOVDD_11") (pintype "bidirectional"))
      (node (ref "U1") (pin "20") (pinfunction "IOVDD_20") (pintype "bidirectional"))
      (node (ref "U1") (pin "30") (pinfunction "IOVDD_30") (pintype "bidirectional"))
      (node (ref "U1") (pin "38") (pinfunction "IOVDD_38") (pintype "bidirectional"))
      (node (ref "U1") (pin "44") (pinfunction "ADC_IOVDD_44") (pintype "bidirectional"))
      (node (ref "U1") (pin "45") (pinfunction "IOVDD_45") (pintype "bidirectional"))
      (node (ref "U1") (pin "49") (pinfunction "VREG_VIN_49") (pintype "bidirectional"))
      (node (ref "U1") (pin "53") (pinfunction "USB_OTP_VDD_53") (pintype "bidirectional"))
      (node (ref "U1") (pin "54") (pinfunction "QSPI_IOVDD_54") (pintype "bidirectional"))
      (node (ref "U15") (pin "1") (pinfunction "VCCA_1") (pintype "power_in"))
      (node (ref "U15") (pin "5") (pinfunction "DIR_5") (pintype "input"))
      (node (ref "U2") (pin "8") (pinfunction "VDD_8") (pintype "bidirectional"))
      (node (ref "U3") (pin "3") (pinfunction "3V3_3") (pintype "power_in"))
      (node (ref "U4") (pin "5") (pinfunction "VOUT_5") (pintype "output"))
      (node (ref "U5") (pin "2") (pinfunction "CSB_2") (pintype "input"))
      (node (ref "U5") (pin "6") (pinfunction "VDDIO_6") (pintype "power_in"))
      (node (ref "U5") (pin "8") (pinfunction "VDD_8") (pintype "power_in"))
      (node (ref "U6") (pin "P4") (pinfunction "VDDP_P4") (pintype "bidirectional"))
      (node (ref "U7") (pin "1") (pinfunction "VDD_1") (pintype "power_in"))
      (node (ref "U8") (pin "8") (pinfunction "C(VCC)_8") (pintype "passive"))
      (node (ref "U9") (pin "15") (pinfunction "ADD0_15") (pintype "input"))
      (node (ref "U9") (pin "16") (pinfunction "ADD1_16") (pintype "input"))
      (node (ref "U9") (pin "5") (pinfunction "VDD_5") (pintype "power_in"))
      (node (ref "U9") (pin "6") (pinfunction "VREG_6") (pintype "power_in"))
      (node (ref "U9") (pin "9") (pinfunction "SI_9") (pintype "input"))
    )
    (net (code "3") (name "BUZZER_DRIVER") (class "Default")
      (node (ref "R25") (pin "2") (pinfunction "2_2") (pintype "passive"))
      (node (ref "U1") (pin "9") (pinfunction "GPIO6_9") (pintype "bidirectional"))
    )
    (net (code "4") (name "CMD") (class "Default")
      (node (ref "U$1") (pin "P3") (pinfunction "CMD_P3") (pintype "bidirectional"))
      (node (ref "U1") (pin "19") (pinfunction "GPIO15_19") (pintype "bidirectional"))
    )
    (net (code "5") (name "DAT0") (class "Default")
      (node (ref "U$1") (pin "P7") (pinfunction "DAT0_P7") (pintype "bidirectional"))
      (node (ref "U1") (pin "16") (pinfunction "GPIO12_16") (pintype "bidirectional"))
    )
    (net (code "6") (name "DAT1") (class "Default")
      (node (ref "U$1") (pin "P8") (pinfunction "DAT1_P8") (pintype "bidirectional"))
      (node (ref "U1") (pin "15") (pinfunction "GPIO11_15") (pintype "bidirectional"))
    )
    (net (code "7") (name "DAT2") (class "Default")
      (node (ref "U$1") (pin "P1") (pinfunction "DAT2_P1") (pintype "bidirectional"))
      (node (ref "U1") (pin "14") (pinfunction "GPIO10_14") (pintype "bidirectional"))
    )
    (net (code "8") (name "DAT3") (class "Default")
      (node (ref "U$1") (pin "P2") (pinfunction "CD/DAT3_P2") (pintype "bidirectional"))
      (node (ref "U1") (pin "17") (pinfunction "GPIO13_17") (pintype "bidirectional"))
    )
    (net (code "9") (name "ESP32_CS") (class "Default")
      (node (ref "U1") (pin "33") (pinfunction "GPIO21_33") (pintype "bidirectional"))
      (node (ref "U3") (pin "16") (pinfunction "IO10_16") (pintype "bidirectional"))
    )
    (net (code "10") (name "ESP32_HANDSHAKE") (class "Default")
      (node (ref "U1") (pin "28") (pinfunction "GPIO17_28") (pintype "bidirectional"))
      (node (ref "U3") (pin "6") (pinfunction "IO3_6") (pintype "bidirectional"))
    )
    (net (code "11") (name "ESP32_MISO") (class "Default")
      (node (ref "U1") (pin "32") (pinfunction "GPIO20_32") (pintype "bidirectional"))
      (node (ref "U3") (pin "5") (pinfunction "IO2_5") (pintype "bidirectional"))
    )
    (net (code "12") (name "ESP32_MOSI") (class "Default")
      (node (ref "U1") (pin "35") (pinfunction "GPIO23_35") (pintype "bidirectional"))
      (node (ref "U3") (pin "21") (pinfunction "IO7_21") (pintype "bidirectional"))
    )
    (net (code "13") (name "ESP32_RX") (class "Default")
      (node (ref "U1") (pin "7") (pinfunction "GPIO4_7") (pintype "bidirectional"))
      (node (ref "U3") (pin "30") (pinfunction "RXD0_30") (pintype "bidirectional"))
    )
    (net (code "14") (name "ESP32_SCK") (class "Default")
      (node (ref "U1") (pin "34") (pinfunction "GPIO22_34") (pintype "bidirectional"))
      (node (ref "U3") (pin "20") (pinfunction "IO6_20") (pintype "bidirectional"))
    )
    (net (code "15") (name "ESP32_TX") (class "Default")
      (node (ref "U1") (pin "8") (pinfunction "GPIO5_8") (pintype "bidirectional"))
      (node (ref "U3") (pin "31") (pinfunction "TXD0_31") (pintype "bidirectional"))
    )
    (net (code "16") (name "GND") (class "Default")
      (node (ref "!BOOT") (pin "1") (pinfunction "1_1") (pintype "passive"))
      (node (ref "!BOOT") (pin "2") (pinfunction "1_2") (pintype "passive"))
      (node (ref "C1") (pin "2") (pinfunction "2_2") (pintype "passive"))
      (node (ref "C10") (pin "2") (pinfunction "2_2") (pintype "passive"))
      (node (ref "C11") (pin "2") (pinfunction "2_2") (pintype "passive"))
      (node (ref "C12") (pin "2") (pinfunction "2_2") (pintype "passive"))
      (node (ref "C13") (pin "2") (pinfunction "2_2") (pintype "passive"))
      (node (ref "C14") (pin "2") (pinfunction "2_2") (pintype "passive"))
      (node (ref "C15") (pin "2") (pinfunction "2_2") (pintype "passive"))
      (node (ref "C16") (pin "2") (pinfunction "2_2") (pintype "passive"))
      (node (ref "C17") (pin "1") (pinfunction "1_1") (pintype "passive"))
      (node (ref "C18") (pin "2") (pinfunction "2_2") (pintype "passive"))
      (node (ref "C19") (pin "2") (pinfunction "2_2") (pintype "passive"))
      (node (ref "C2") (pin "2") (pinfunction "2_2") (pintype "passive"))
      (node (ref "C20") (pin "2") (pinfunction "2_2") (pintype "passive"))
      (node (ref "C21") (pin "2") (pinfunction "2_2") (pintype "passive"))
      (node (ref "C22") (pin "2") (pinfunction "2_2") (pintype "passive"))
      (node (ref "C23") (pin "1") (pinfunction "1_1") (pintype "passive"))
      (node (ref "C24") (pin "1") (pinfunction "1_1") (pintype "passive"))
      (node (ref "C25") (pin "2") (pinfunction "2_2") (pintype "passive"))
      (node (ref "C26") (pin "2") (pinfunction "2_2") (pintype "passive"))
      (node (ref "C27") (pin "2") (pinfunction "2_2") (pintype "passive"))
      (node (ref "C28") (pin "2") (pinfunction "2_2") (pintype "passive"))
      (node (ref "C29") (pin "2") (pinfunction "2_2") (pintype "passive"))
      (node (ref "C3") (pin "2") (pinfunction "2_2") (pintype "passive"))
      (node (ref "C30") (pin "2") (pinfunction "2_2") (pintype "passive"))
      (node (ref "C31") (pin "2") (pinfunction "2_2") (pintype "passive"))
      (node (ref "C32") (pin "2") (pinfunction "2_2") (pintype "passive"))
      (node (ref "C33") (pin "2") (pinfunction "2_2") (pintype "passive"))
      (node (ref "C34") (pin "1") (pinfunction "1_1") (pintype "passive"))
      (node (ref "C35") (pin "1") (pinfunction "1_1") (pintype "passive"))
      (node (ref "C36") (pin "1") (pinfunction "1_1") (pintype "passive"))
      (node (ref "C4") (pin "2") (pinfunction "2_2") (pintype "passive"))
      (node (ref "C42") (pin "1") (pinfunction "1_1") (pintype "passive"))
      (node (ref "C43") (pin "2") (pinfunction "-_2") (pintype "bidirectional"))
      (node (ref "C44") (pin "1") (pinfunction "1_1") (pintype "passive"))
      (node (ref "C45") (pin "2") (pinfunction "2_2") (pintype "passive"))
      (node (ref "C46") (pin "2") (pinfunction "2_2") (pintype "passive"))
      (node (ref "C47") (pin "1") (pinfunction "1_1") (pintype "passive"))
      (node (ref "C48") (pin "1") (pinfunction "1_1") (pintype "passive"))
      (node (ref "C49") (pin "2") (pinfunction "2_2") (pintype "passive"))
      (node (ref "C5") (pin "2") (pinfunction "2_2") (pintype "passive"))
      (node (ref "C50") (pin "2") (pinfunction "2_2") (pintype "passive"))
      (node (ref "C51") (pin "2") (pinfunction "2_2") (pintype "passive"))
      (node (ref "C52") (pin "2") (pinfunction "2_2") (pintype "passive"))
      (node (ref "C6") (pin "2") (pinfunction "2_2") (pintype "passive"))
      (node (ref "C7") (pin "2") (pinfunction "2_2") (pintype "passive"))
      (node (ref "C8") (pin "2") (pinfunction "2_2") (pintype "passive"))
      (node (ref "C9") (pin "2") (pinfunction "2_2") (pintype "passive"))
      (node (ref "GND") (pin "TP") (pinfunction "TP_TP") (pintype "input"))
      (node (ref "IC1") (pin "4") (pinfunction "GND_4") (pintype "bidirectional"))
      (node (ref "IC1") (pin "9") (pinfunction "EP_9") (pintype "bidirectional"))
      (node (ref "J1") (pin "2") (pinfunction "2_2") (pintype "passive"))
      (node (ref "J1") (pin "S1") (pinfunction "SHIELD_S1") (pintype "passive"))
      (node (ref "J1") (pin "S2") (pinfunction "SHIELD_S2") (pintype "passive"))
      (node (ref "J2") (pin "A1_B12") (pinfunction "GND_A1_B12") (pintype "power_in"))
      (node (ref "J2") (pin "B1_A12") (pinfunction "GND_B1_A12") (pintype "power_in"))
      (node (ref "J2") (pin "S1") (pinfunction "SHIELD_S1") (pintype "passive"))
      (node (ref "J2") (pin "S2") (pinfunction "SHIELD_S2") (pintype "passive"))
      (node (ref "J2") (pin "S3") (pinfunction "SHIELD_S3") (pintype "passive"))
      (node (ref "J2") (pin "S4") (pinfunction "SHIELD_S4") (pintype "passive"))
      (node (ref "J3") (pin "1") (pinfunction "1_1") (pintype "power_in"))
      (node (ref "L3") (pin "1") (pinfunction "1_1") (pintype "passive"))
      (node (ref "Q1") (pin "2") (pinfunction "S_2") (pintype "bidirectional"))
      (node (ref "Q2") (pin "2") (pinfunction "S_2") (pintype "bidirectional"))
      (node (ref "R10") (pin "1") (pinfunction "1_1") (pintype "passive"))
      (node (ref "R18") (pin "1") (pinfunction "1_1") (pintype "passive"))
      (node (ref "R2") (pin "2") (pinfunction "2_2") (pintype "passive"))
      (node (ref "R9") (pin "1") (pinfunction "1_1") (pintype "passive"))
      (node (ref "U$1") (pin "P$1") (pinfunction "GND_P$1") (pintype "power_in"))
      (node (ref "U$1") (pin "P$2") (pinfunction "GND_P$2") (pintype "power_in"))
      (node (ref "U$1") (pin "P$3") (pinfunction "GND_P$3") (pintype "power_in"))
      (node (ref "U$1") (pin "P$4") (pinfunction "GND_P$4") (pintype "power_in"))
      (node (ref "U$1") (pin "P6") (pinfunction "GND_P6") (pintype "power_in"))
      (node (ref "U1") (pin "47") (pinfunction "VREG_GND_47") (pintype "bidirectional"))
      (node (ref "U1") (pin "EPAD") (pinfunction "GND_EPAD") (pintype "bidirectional"))
      (node (ref "U10") (pin "4") (pinfunction "VSS_4") (pintype "power_in"))
      (node (ref "U11") (pin "P$3") (pinfunction "GND_P$3") (pintype "bidirectional"))
      (node (ref "U12") (pin "P$3") (pinfunction "GND_P$3") (pintype "bidirectional"))
      (node (ref "U13") (pin "P$3") (pinfunction "GND_P$3") (pintype "bidirectional"))
      (node (ref "U14") (pin "P$3") (pinfunction "GND_P$3") (pintype "bidirectional"))
      (node (ref "U15") (pin "2") (pinfunction "GND_2") (pintype "power_in"))
      (node (ref "U2") (pin "4") (pinfunction "VSS_4") (pintype "bidirectional"))
      (node (ref "U2") (pin "9") (pinfunction "VSS_9") (pintype "bidirectional"))
      (node (ref "U3") (pin "1") (pinfunction "GND_1") (pintype "power_in"))
      (node (ref "U3") (pin "11") (pinfunction "GND_11") (pintype "power_in"))
      (node (ref "U3") (pin "14") (pinfunction "GND_14") (pintype "power_in"))
      (node (ref "U3") (pin "2") (pinfunction "GND_2") (pintype "power_in"))
      (node (ref "U3") (pin "36") (pinfunction "GND_36") (pintype "power_in"))
      (node (ref "U3") (pin "37") (pinfunction "GND_37") (pintype "power_in"))
      (node (ref "U3") (pin "38") (pinfunction "GND_38") (pintype "power_in"))
      (node (ref "U3") (pin "39") (pinfunction "GND_39") (pintype "power_in"))
      (node (ref "U3") (pin "40") (pinfunction "GND_40") (pintype "power_in"))
      (node (ref "U3") (pin "41") (pinfunction "GND_41") (pintype "power_in"))
      (node (ref "U3") (pin "42") (pinfunction "GND_42") (pintype "power_in"))
      (node (ref "U3") (pin "43") (pinfunction "GND_43") (pintype "power_in"))
      (node (ref "U3") (pin "44") (pinfunction "GND_44") (pintype "power_in"))
      (node (ref "U3") (pin "45") (pinfunction "GND_45") (pintype "power_in"))
      (node (ref "U3") (pin "46") (pinfunction "GND_46") (pintype "power_in"))
      (node (ref "U3") (pin "47") (pinfunction "GND_47") (pintype "power_in"))
      (node (ref "U3") (pin "48") (pinfunction "GND_48") (pintype "power_in"))
      (node (ref "U3") (pin "49_1") (pinfunction "GND_49_1") (pintype "power_in"))
      (node (ref "U3") (pin "49_2") (pinfunction "GND_49_2") (pintype "power_in"))
      (node (ref "U3") (pin "49_3") (pinfunction "GND_49_3") (pintype "power_in"))
      (node (ref "U3") (pin "49_4") (pinfunction "GND_49_4") (pintype "power_in"))
      (node (ref "U3") (pin "49_5") (pinfunction "GND_49_5") (pintype "power_in"))
      (node (ref "U3") (pin "49_6") (pinfunction "GND_49_6") (pintype "power_in"))
      (node (ref "U3") (pin "49_7") (pinfunction "GND_49_7") (pintype "power_in"))
      (node (ref "U3") (pin "49_8") (pinfunction "GND_49_8") (pintype "power_in"))
      (node (ref "U3") (pin "49_9") (pinfunction "GND_49_9") (pintype "power_in"))
      (node (ref "U3") (pin "50") (pinfunction "GND_50") (pintype "power_in"))
      (node (ref "U3") (pin "51") (pinfunction "GND_51") (pintype "power_in"))
      (node (ref "U3") (pin "52") (pinfunction "GND_52") (pintype "power_in"))
      (node (ref "U3") (pin "53") (pinfunction "GND_53") (pintype "power_in"))
      (node (ref "U4") (pin "2") (pinfunction "GND_2") (pintype "power_in"))
      (node (ref "U5") (pin "1") (pinfunction "GND_1") (pintype "power_in"))
      (node (ref "U5") (pin "5") (pinfunction "SDO_5") (pintype "bidirectional"))
      (node (ref "U5") (pin "7") (pinfunction "GND_7") (pintype "power_in"))
      (node (ref "U6") (pin "P1") (pinfunction "GNDP_P1") (pintype "bidirectional"))
      (node (ref "U6") (pin "P10") (pinfunction "GNDP_P10") (pintype "bidirectional"))
      (node (ref "U6") (pin "P5") (pinfunction "GNDP_P5") (pintype "bidirectional"))
      (node (ref "U6") (pin "P7") (pinfunction "GNDP_P7") (pintype "bidirectional"))
      (node (ref "U7") (pin "4") (pinfunction "VSS_4") (pintype "power_in"))
      (node (ref "U7") (pin "5") (pinfunction "VSS_5") (pintype "power_in"))
      (node (ref "U8") (pin "5") (pinfunction "E(GND)_5") (pintype "passive"))
      (node (ref "U9") (pin "12") (pinfunction "MISO_12") (pintype "output"))
      (node (ref "U9") (pin "17") (pinfunction "EXP_17") (pintype "power_in"))
      (node (ref "U9") (pin "2") (pinfunction "INN_2") (pintype "bidirectional"))
      (node (ref "U9") (pin "4") (pinfunction "GND_4") (pintype "power_in"))
      (node (ref "U9") (pin "7") (pinfunction "EN_VREG_7") (pintype "input"))
      (node (ref "U9") (pin "8") (pinfunction "~{CS}_8") (pintype "input"))
      (node (ref "USR_BUTTON") (pin "3") (pinfunction "2_3") (pintype "passive"))
      (node (ref "USR_BUTTON") (pin "4") (pinfunction "2_4") (pintype "passive"))
      (node (ref "Y1") (pin "2") (pinfunction "GND_2") (pintype "power_in"))
      (node (ref "Y1") (pin "4") (pinfunction "GND_4") (pintype "power_in"))
    )
    (net (code "17") (name "GND-ISO") (class "Default")
      (node (ref "C37") (pin "2") (pinfunction "2_2") (pintype "passive"))
      (node (ref "C38") (pin "2") (pinfunction "2_2") (pintype "passive"))
      (node (ref "C39") (pin "2") (pinfunction "2_2") (pintype "passive"))
      (node (ref "C40") (pin "1") (pinfunction "1_1") (pintype "passive"))
      (node (ref "C41") (pin "1") (pinfunction "1_1") (pintype "passive"))
      (node (ref "R20") (pin "1") (pinfunction "1_1") (pintype "passive"))
      (node (ref "U$2") (pin "P$6") (pinfunction "GND_P$6") (pintype "power_in"))
      (node (ref "U$3") (pin "P$6") (pinfunction "GND_P$6") (pintype "power_in"))
      (node (ref "U6") (pin "P11") (pinfunction "GNDISO_P11") (pintype "bidirectional"))
      (node (ref "U6") (pin "P14") (pinfunction "GNDISO_P14") (pintype "bidirectional"))
      (node (ref "U6") (pin "P16") (pinfunction "GNDISO_P16") (pintype "bidirectional"))
      (node (ref "U6") (pin "P20") (pinfunction "GNDISO_P20") (pintype "bidirectional"))
      (node (ref "U8") (pin "2") (pinfunction "C1_2") (pintype "passive"))
      (node (ref "U8") (pin "3") (pinfunction "C2_3") (pintype "passive"))
    )
    (net (code "18") (name "INT_RTC") (class "Default")
      (node (ref "U1") (pin "40") (pinfunction "GPIO26/ADC0_40") (pintype "bidirectional"))
      (node (ref "U10") (pin "3") (pinfunction "~{INT}_3") (pintype "output"))
    )
    (net (code "19") (name "INT_SOIL") (class "Default")
      (node (ref "R14") (pin "1") (pinfunction "1_1") (pintype "passive"))
      (node (ref "U1") (pin "3") (pinfunction "GPIO1_3") (pintype "bidirectional"))
      (node (ref "U8") (pin "7") (pinfunction "C1(VO1)_7") (pintype "passive"))
    )
    (net (code "20") (name "INT_SOILTEMP") (class "Default")
      (node (ref "R15") (pin "1") (pinfunction "1_1") (pintype "passive"))
      (node (ref "U1") (pin "4") (pinfunction "GPIO2_4") (pintype "bidirectional"))
      (node (ref "U8") (pin "6") (pinfunction "C2(VO2)_6") (pintype "passive"))
    )
    (net (code "21") (name "INT_SOILTEMP_ISO") (class "Default")
      (node (ref "R16") (pin "1") (pinfunction "1_1") (pintype "passive"))
      (node (ref "U$3") (pin "P$7") (pinfunction "INT_P$7") (pintype "bidirectional"))
    )
    (net (code "22") (name "INT_SOIL_ISO") (class "Default")
      (node (ref "R17") (pin "1") (pinfunction "1_1") (pintype "passive"))
      (node (ref "U$2") (pin "P$7") (pinfunction "INT_P$7") (pintype "bidirectional"))
    )
    (net (code "23") (name "IRQ_LIGHTNING") (class "Default")
      (node (ref "U1") (pin "10") (pinfunction "GPIO7_10") (pintype "bidirectional"))
      (node (ref "U9") (pin "10") (pinfunction "IRQ_10") (pintype "output"))
    )
    (net (code "24") (name "NEOPIXEL_3.3V") (class "Default")
      (node (ref "U1") (pin "27") (pinfunction "GPIO16_27") (pintype "bidirectional"))
      (node (ref "U15") (pin "3") (pinfunction "A_3") (pintype "input"))
    )
    (net (code "25") (name "NEOPIXEL_5V") (class "Default")
      (node (ref "U11") (pin "P$4") (pinfunction "DI_P$4") (pintype "bidirectional"))
      (node (ref "U15") (pin "4") (pinfunction "B_4") (pintype "output"))
    )
    (net (code "26") (name "Net-(C21-Pad1)") (class "Default")
      (node (ref "C21") (pin "1") (pinfunction "1_1") (pintype "passive"))
      (node (ref "J2") (pin "A4_B9") (pinfunction "VBUS_A4_B9") (pintype "power_in"))
      (node (ref "J2") (pin "B4_A9") (pinfunction "VBUS_B4_A9") (pintype "power_in"))
      (node (ref "L2") (pin "1") (pinfunction "1_1") (pintype "passive"))
    )
    (net (code "27") (name "Net-(C43-+)") (class "Default")
      (node (ref "C43") (pin "1") (pinfunction "+_1") (pintype "bidirectional"))
      (node (ref "C46") (pin "1") (pinfunction "1_1") (pintype "passive"))
      (node (ref "D2") (pin "C") (pinfunction "C_C") (pintype "passive"))
      (node (ref "U10") (pin "8") (pinfunction "VDD_8") (pintype "power_in"))
    )
    (net (code "28") (name "Net-(J2-CC1)") (class "Default")
      (node (ref "J2") (pin "A5") (pinfunction "CC1_A5") (pintype "bidirectional"))
      (node (ref "R10") (pin "2") (pinfunction "2_2") (pintype "passive"))
    )
    (net (code "29") (name "Net-(J2-CC2)") (class "Default")
      (node (ref "J2") (pin "B5") (pinfunction "CC2_B5") (pintype "bidirectional"))
      (node (ref "R9") (pin "2") (pinfunction "2_2") (pintype "passive"))
    )
    (net (code "30") (name "Net-(L4-P$1)") (class "Default")
      (node (ref "L4") (pin "1") (pinfunction "P$1_1") (pintype "bidirectional"))
      (node (ref "U1") (pin "48") (pinfunction "VREG_LX_48") (pintype "bidirectional"))
    )
    (net (code "31") (name "Net-(Q2-D)") (class "Default")
      (node (ref "D1") (pin "A") (pinfunction "A_A") (pintype "passive"))
      (node (ref "LS1") (pin "N") (pinfunction "N_N") (pintype "passive"))
      (node (ref "Q2") (pin "3") (pinfunction "D_3") (pintype "bidirectional"))
    )
    (net (code "32") (name "Net-(Q2-G)") (class "Default")
      (node (ref "Q2") (pin "1") (pinfunction "G_1") (pintype "bidirectional"))
      (node (ref "R25") (pin "1") (pinfunction "1_1") (pintype "passive"))
    )
    (net (code "33") (name "Net-(R2-Pad1)") (class "Default")
      (node (ref "R2") (pin "1") (pinfunction "1_1") (pintype "passive"))
      (node (ref "RESET") (pin "3") (pinfunction "2_3") (pintype "passive"))
      (node (ref "RESET") (pin "4") (pinfunction "2_4") (pintype "passive"))
    )
    (net (code "34") (name "Net-(U1-GPIO3)") (class "Default")
      (node (ref "U1") (pin "5") (pinfunction "GPIO3_5") (pintype "bidirectional"))
      (node (ref "USR_BUTTON") (pin "1") (pinfunction "1_1") (pintype "passive"))
      (node (ref "USR_BUTTON") (pin "2") (pinfunction "1_2") (pintype "passive"))
    )
    (net (code "35") (name "Net-(U1-USB_D+)") (class "Default")
      (node (ref "R3") (pin "2") (pinfunction "2_2") (pintype "passive"))
      (node (ref "U1") (pin "52") (pinfunction "USB_D+_52") (pintype "bidirectional"))
    )
    (net (code "36") (name "Net-(U1-USB_D-)") (class "Default")
      (node (ref "R4") (pin "2") (pinfunction "2_2") (pintype "passive"))
      (node (ref "U1") (pin "51") (pinfunction "USB_D-_51") (pintype "bidirectional"))
    )
    (net (code "37") (name "Net-(U1-VREG_AVDD)") (class "Default")
      (node (ref "C10") (pin "1") (pinfunction "1_1") (pintype "passive"))
      (node (ref "R1") (pin "2") (pinfunction "2_2") (pintype "passive"))
      (node (ref "U1") (pin "46") (pinfunction "VREG_AVDD_46") (pintype "bidirectional"))
    )
    (net (code "38") (name "Net-(U1-XIN)") (class "Default")
      (node (ref "C19") (pin "1") (pinfunction "1_1") (pintype "passive"))
      (node (ref "U1") (pin "21") (pinfunction "XIN_21") (pintype "bidirectional"))
      (node (ref "Y1") (pin "1") (pinfunction "1_1") (pintype "passive"))
    )
    (net (code "39") (name "Net-(U1-XOUT)") (class "Default")
      (node (ref "R8") (pin "2") (pinfunction "2_2") (pintype "passive"))
      (node (ref "U1") (pin "22") (pinfunction "XOUT_22") (pintype "bidirectional"))
    )
    (net (code "40") (name "Net-(U3-IO8)") (class "Default")
      (node (ref "R13") (pin "1") (pinfunction "1_1") (pintype "passive"))
      (node (ref "U3") (pin "22") (pinfunction "IO8_22") (pintype "bidirectional"))
    )
    (net (code "41") (name "Net-(U6-VSEL)") (class "Default")
      (node (ref "R19") (pin "1") (pinfunction "1_1") (pintype "passive"))
      (node (ref "R20") (pin "2") (pinfunction "2_2") (pintype "passive"))
      (node (ref "U6") (pin "P13") (pinfunction "VSEL_P13") (pintype "bidirectional"))
    )
    (net (code "42") (name "Net-(U8-A1)") (class "Default")
      (node (ref "R17") (pin "2") (pinfunction "2_2") (pintype "passive"))
      (node (ref "U8") (pin "1") (pinfunction "A1_1") (pintype "passive"))
    )
    (net (code "43") (name "Net-(U8-A2)") (class "Default")
      (node (ref "R16") (pin "2") (pinfunction "2_2") (pintype "passive"))
      (node (ref "U8") (pin "4") (pinfunction "A2_4") (pintype "passive"))
    )
    (net (code "44") (name "Net-(U9-ACG)") (class "Default")
      (node (ref "C31") (pin "1") (pinfunction "1_1") (pintype "passive"))
      (node (ref "U9") (pin "1") (pinfunction "ACG_1") (pintype "passive"))
    )
    (net (code "45") (name "Net-(U9-INP)") (class "Default")
      (node (ref "C33") (pin "1") (pinfunction "1_1") (pintype "passive"))
      (node (ref "L3") (pin "2") (pinfunction "2_2") (pintype "passive"))
      (node (ref "R18") (pin "2") (pinfunction "2_2") (pintype "passive"))
      (node (ref "U9") (pin "3") (pinfunction "INP_3") (pintype "bidirectional"))
    )
    (net (code "46") (name "Net-(U10-OSCI)") (class "Default")
      (node (ref "C47") (pin "2") (pinfunction "2_2") (pintype "passive"))
      (node (ref "U10") (pin "1") (pinfunction "OSCI_1") (pintype "input"))
      (node (ref "XTAL1") (pin "2") (pinfunction "2_2") (pintype "passive"))
    )
    (net (code "47") (name "Net-(U10-OSCO)") (class "Default")
      (node (ref "C48") (pin "2") (pinfunction "2_2") (pintype "passive"))
      (node (ref "U10") (pin "2") (pinfunction "OSCO_2") (pintype "output"))
      (node (ref "XTAL1") (pin "1") (pinfunction "1_1") (pintype "passive"))
    )
    (net (code "48") (name "Net-(U11-DO)") (class "Default")
      (node (ref "U11") (pin "P$2") (pinfunction "DO_P$2") (pintype "bidirectional"))
      (node (ref "U12") (pin "P$4") (pinfunction "DI_P$4") (pintype "bidirectional"))
    )
    (net (code "49") (name "Net-(U12-DO)") (class "Default")
      (node (ref "U12") (pin "P$2") (pinfunction "DO_P$2") (pintype "bidirectional"))
      (node (ref "U13") (pin "P$4") (pinfunction "DI_P$4") (pintype "bidirectional"))
    )
    (net (code "50") (name "Net-(U13-DO)") (class "Default")
      (node (ref "U13") (pin "P$2") (pinfunction "DO_P$2") (pintype "bidirectional"))
      (node (ref "U14") (pin "P$4") (pinfunction "DI_P$4") (pintype "bidirectional"))
    )
    (net (code "51") (name "Net-(Y1-2)") (class "Default")
      (node (ref "C18") (pin "1") (pinfunction "1_1") (pintype "passive"))
      (node (ref "R8") (pin "1") (pinfunction "1_1") (pintype "passive"))
      (node (ref "Y1") (pin "3") (pinfunction "2_3") (pintype "passive"))
    )
    (net (code "52") (name "PDIS") (class "Default")
      (node (ref "Q1") (pin "3") (pinfunction "D_3") (pintype "bidirectional"))
      (node (ref "R23") (pin "1") (pinfunction "1_1") (pintype "passive"))
      (node (ref "U6") (pin "P8") (pinfunction "PDIS_P8") (pintype "bidirectional"))
    )
    (net (code "53") (name "PDIS_EN") (class "Default")
      (node (ref "Q1") (pin "1") (pinfunction "G_1") (pintype "bidirectional"))
      (node (ref "R24") (pin "1") (pinfunction "1_1") (pintype "passive"))
      (node (ref "U1") (pin "12") (pinfunction "GPIO8_12") (pintype "bidirectional"))
    )
    (net (code "54") (name "PRB1") (class "Default")
      (node (ref "J4") (pin "1") (pinfunction "1_1") (pintype "passive"))
      (node (ref "U$2") (pin "P$4") (pinfunction "PRB_P$4") (pintype "bidirectional"))
    )
    (net (code "55") (name "PRB1_GND") (class "Default")
      (node (ref "J4") (pin "2") (pinfunction "2_2") (pintype "passive"))
      (node (ref "J4") (pin "3") (pinfunction "2_3") (pintype "passive"))
      (node (ref "U$2") (pin "P$5") (pinfunction "PRB_GND_P$5") (pintype "bidirectional"))
    )
    (net (code "56") (name "PROBE2") (class "Default")
      (node (ref "J5") (pin "1") (pinfunction "1_1") (pintype "passive"))
      (node (ref "U$3") (pin "P$4") (pinfunction "PRB_P$4") (pintype "bidirectional"))
    )
    (net (code "57") (name "PROBE2_GND") (class "Default")
      (node (ref "J5") (pin "2") (pinfunction "2_2") (pintype "passive"))
      (node (ref "J5") (pin "3") (pinfunction "2_3") (pintype "passive"))
      (node (ref "U$3") (pin "P$5") (pinfunction "PRB_GND_P$5") (pintype "bidirectional"))
    )
    (net (code "58") (name "QSPI_CLK") (class "Default")
      (node (ref "IC1") (pin "6") (pinfunction "CLK_6") (pintype "bidirectional"))
      (node (ref "U1") (pin "56") (pinfunction "QSPI_SCLK_56") (pintype "bidirectional"))
      (node (ref "U2") (pin "6") (pinfunction "SCLK_6") (pintype "bidirectional"))
    )
    (net (code "59") (name "SCL") (class "Default")
      (node (ref "J3") (pin "4") (pinfunction "4_4") (pintype "passive"))
      (node (ref "R12") (pin "1") (pinfunction "1_1") (pintype "passive"))
      (node (ref "U1") (pin "37") (pinfunction "GPIO25_37") (pintype "bidirectional"))
      (node (ref "U10") (pin "6") (pinfunction "SCL_6") (pintype "input"))
      (node (ref "U5") (pin "4") (pinfunction "SCK_4") (pintype "input"))
      (node (ref "U6") (pin "P2") (pinfunction "SCL2_P2") (pintype "bidirectional"))
      (node (ref "U7") (pin "2") (pinfunction "SCL_2") (pintype "input"))
      (node (ref "U9") (pin "11") (pinfunction "I2CL/SCL_11") (pintype "input"))
    )
    (net (code "60") (name "SCL_ISO") (class "Default")
      (node (ref "R22") (pin "1") (pinfunction "1_1") (pintype "passive"))
      (node (ref "U$2") (pin "P$8") (pinfunction "SCL_P$8") (pintype "bidirectional"))
      (node (ref "U$3") (pin "P$8") (pinfunction "SCL_P$8") (pintype "bidirectional"))
      (node (ref "U6") (pin "P19") (pinfunction "SCL1_P19") (pintype "bidirectional"))
    )
    (net (code "61") (name "SDA") (class "Default")
      (node (ref "J3") (pin "3") (pinfunction "3_3") (pintype "passive"))
      (node (ref "R11") (pin "1") (pinfunction "1_1") (pintype "passive"))
      (node (ref "U1") (pin "36") (pinfunction "GPIO24_36") (pintype "bidirectional"))
      (node (ref "U10") (pin "5") (pinfunction "SDA_5") (pintype "bidirectional"))
      (node (ref "U5") (pin "3") (pinfunction "SDI_3") (pintype "bidirectional"))
      (node (ref "U6") (pin "P3") (pinfunction "SDA2_P3") (pintype "bidirectional"))
      (node (ref "U7") (pin "3") (pinfunction "SDA_3") (pintype "bidirectional"))
      (node (ref "U9") (pin "13") (pinfunction "I2CD/MOSI_13") (pintype "bidirectional"))
    )
    (net (code "62") (name "SDA_ISO") (class "Default")
      (node (ref "R21") (pin "1") (pinfunction "1_1") (pintype "passive"))
      (node (ref "U$2") (pin "P$1") (pinfunction "SDA_P$1") (pintype "bidirectional"))
      (node (ref "U$3") (pin "P$1") (pinfunction "SDA_P$1") (pintype "bidirectional"))
      (node (ref "U6") (pin "P18") (pinfunction "SDA1_P18") (pintype "bidirectional"))
    )
    (net (code "63") (name "SD_CLK") (class "Default")
      (node (ref "U$1") (pin "P5") (pinfunction "CLK_P5") (pintype "bidirectional"))
      (node (ref "U1") (pin "18") (pinfunction "GPIO14_18") (pintype "bidirectional"))
    )
    (net (code "64") (name "SIO0") (class "Default")
      (node (ref "IC1") (pin "5") (pinfunction "DI(IO0)_5") (pintype "bidirectional"))
      (node (ref "U1") (pin "57") (pinfunction "QSPI_SD0_57") (pintype "bidirectional"))
      (node (ref "U2") (pin "5") (pinfunction "SI/SIO0_5") (pintype "bidirectional"))
    )
    (net (code "65") (name "SIO1") (class "Default")
      (node (ref "IC1") (pin "2") (pinfunction "DO(IO1)_2") (pintype "bidirectional"))
      (node (ref "U1") (pin "59") (pinfunction "QSPI_SD1_59") (pintype "bidirectional"))
      (node (ref "U2") (pin "2") (pinfunction "SO/SIO1_2") (pintype "bidirectional"))
    )
    (net (code "66") (name "SIO2") (class "Default")
      (node (ref "IC1") (pin "3") (pinfunction "~{WP(IO2})_3") (pintype "bidirectional"))
      (node (ref "U1") (pin "58") (pinfunction "QSPI_SD2_58") (pintype "bidirectional"))
      (node (ref "U2") (pin "3") (pinfunction "SIO2_3") (pintype "bidirectional"))
    )
    (net (code "67") (name "SIO3") (class "Default")
      (node (ref "IC1") (pin "7") (pinfunction "~{HOLD_OR_}RESET_(IO3)_7") (pintype "bidirectional"))
      (node (ref "U1") (pin "55") (pinfunction "QSPI_SD3_55") (pintype "bidirectional"))
      (node (ref "U2") (pin "7") (pinfunction "SIO3_7") (pintype "bidirectional"))
    )
    (net (code "68") (name "SWCLK") (class "Default")
      (node (ref "J1") (pin "1") (pinfunction "1_1") (pintype "passive"))
      (node (ref "U1") (pin "24") (pinfunction "SWCLK_24") (pintype "bidirectional"))
    )
    (net (code "69") (name "SWDIO") (class "Default")
      (node (ref "J1") (pin "3") (pinfunction "3_3") (pintype "passive"))
      (node (ref "U1") (pin "25") (pinfunction "SWDIO_25") (pintype "bidirectional"))
    )
    (net (code "70") (name "SWITCH") (class "Default")
      (node (ref "U$1") (pin "G1") (pinfunction "SWITCH_G1") (pintype "bidirectional"))
      (node (ref "U1") (pin "13") (pinfunction "GPIO9_13") (pintype "bidirectional"))
    )
    (net (code "71") (name "USB_N") (class "Default")
      (node (ref "J2") (pin "A7") (pinfunction "DN1_A7") (pintype "bidirectional"))
      (node (ref "J2") (pin "B7") (pinfunction "DN2_B7") (pintype "bidirectional"))
      (node (ref "R4") (pin "1") (pinfunction "1_1") (pintype "passive"))
    )
    (net (code "72") (name "USB_P") (class "Default")
      (node (ref "J2") (pin "A6") (pinfunction "DP1_A6") (pintype "bidirectional"))
      (node (ref "J2") (pin "B6") (pinfunction "DP2_B6") (pintype "bidirectional"))
      (node (ref "R3") (pin "1") (pinfunction "1_1") (pintype "passive"))
    )
    (net (code "73") (name "VCC-ISO") (class "Default")
      (node (ref "C37") (pin "1") (pinfunction "1_1") (pintype "passive"))
      (node (ref "C38") (pin "1") (pinfunction "1_1") (pintype "passive"))
      (node (ref "C39") (pin "1") (pinfunction "1_1") (pintype "passive"))
      (node (ref "C40") (pin "2") (pinfunction "2_2") (pintype "passive"))
      (node (ref "C41") (pin "2") (pinfunction "2_2") (pintype "passive"))
      (node (ref "R19") (pin "2") (pinfunction "2_2") (pintype "passive"))
      (node (ref "R21") (pin "2") (pinfunction "2_2") (pintype "passive"))
      (node (ref "R22") (pin "2") (pinfunction "2_2") (pintype "passive"))
      (node (ref "U$2") (pin "P$3") (pinfunction "VCC_P$3") (pintype "power_in"))
      (node (ref "U$3") (pin "P$3") (pinfunction "VCC_P$3") (pintype "power_in"))
      (node (ref "U6") (pin "P12") (pinfunction "VISO_P12") (pintype "bidirectional"))
      (node (ref "U6") (pin "P17") (pinfunction "VDDISO_P17") (pintype "bidirectional"))
    )
    (net (code "74") (name "V_USB") (class "Default")
      (node (ref "C22") (pin "1") (pinfunction "1_1") (pintype "passive"))
      (node (ref "C23") (pin "2") (pinfunction "2_2") (pintype "passive"))
      (node (ref "C34") (pin "2") (pinfunction "2_2") (pintype "passive"))
      (node (ref "C35") (pin "2") (pinfunction "2_2") (pintype "passive"))
      (node (ref "C45") (pin "1") (pinfunction "1_1") (pintype "passive"))
      (node (ref "C49") (pin "1") (pinfunction "1_1") (pintype "passive"))
      (node (ref "C50") (pin "1") (pinfunction "1_1") (pintype "passive"))
      (node (ref "C51") (pin "1") (pinfunction "1_1") (pintype "passive"))
      (node (ref "C52") (pin "1") (pinfunction "1_1") (pintype "passive"))
      (node (ref "L2") (pin "2") (pinfunction "2_2") (pintype "passive"))
      (node (ref "R23") (pin "2") (pinfunction "2_2") (pintype "passive"))
      (node (ref "U11") (pin "P$1") (pinfunction "VCC_P$1") (pintype "bidirectional"))
      (node (ref "U12") (pin "P$1") (pinfunction "VCC_P$1") (pintype "bidirectional"))
      (node (ref "U13") (pin "P$1") (pinfunction "VCC_P$1") (pintype "bidirectional"))
      (node (ref "U14") (pin "P$1") (pinfunction "VCC_P$1") (pintype "bidirectional"))
      (node (ref "U15") (pin "6") (pinfunction "VCCB_6") (pintype "power_in"))
      (node (ref "U4") (pin "1") (pinfunction "VIN_1") (pintype "input"))
      (node (ref "U4") (pin "3") (pinfunction "EN_3") (pintype "input"))
      (node (ref "U6") (pin "P9") (pinfunction "VIN_P9") (pintype "bidirectional"))
      (node (ref "USB") (pin "TP") (pinfunction "TP_TP") (pintype "input"))
    )
    (net (code "75") (name "unconnected-(J2-SBU1-PadA8)") (class "Default")
      (node (ref "J2") (pin "A8") (pinfunction "SBU1_A8") (pintype "bidirectional"))
    )
    (net (code "76") (name "unconnected-(J2-SBU2-PadB8)") (class "Default")
      (node (ref "J2") (pin "B8") (pinfunction "SBU2_B8") (pintype "bidirectional"))
    )
    (net (code "77") (name "unconnected-(J6-Pad01)") (class "Default")
      (node (ref "J6") (pin "01") (pinfunction "01_01") (pintype "passive"))
    )
    (net (code "78") (name "unconnected-(J6-Pad02)") (class "Default")
      (node (ref "J6") (pin "02") (pinfunction "02_02") (pintype "passive"))
    )
    (net (code "79") (name "unconnected-(U$2-NC-PadP$2)") (class "Default")
      (node (ref "U$2") (pin "P$2") (pinfunction "NC_P$2") (pintype "no_connect"))
    )
    (net (code "80") (name "unconnected-(U$2-NC-PadP$9)") (class "Default")
      (node (ref "U$2") (pin "P$9") (pinfunction "NC_P$9") (pintype "no_connect"))
    )
    (net (code "81") (name "unconnected-(U$2-NC-PadP$10)") (class "Default")
      (node (ref "U$2") (pin "P$10") (pinfunction "NC_P$10") (pintype "no_connect"))
    )
    (net (code "82") (name "unconnected-(U$3-NC-PadP$2)") (class "Default")
      (node (ref "U$3") (pin "P$2") (pinfunction "NC_P$2") (pintype "no_connect"))
    )
    (net (code "83") (name "unconnected-(U$3-NC-PadP$9)") (class "Default")
      (node (ref "U$3") (pin "P$9") (pinfunction "NC_P$9") (pintype "no_connect"))
    )
    (net (code "84") (name "unconnected-(U$3-NC-PadP$10)") (class "Default")
      (node (ref "U$3") (pin "P$10") (pinfunction "NC_P$10") (pintype "no_connect"))
    )
    (net (code "85") (name "unconnected-(U1-GPIO27{slash}ADC1-Pad41)") (class "Default")
      (node (ref "U1") (pin "41") (pinfunction "GPIO27/ADC1_41") (pintype "bidirectional"))
    )
    (net (code "86") (name "unconnected-(U1-GPIO28{slash}ADC2-Pad42)") (class "Default")
      (node (ref "U1") (pin "42") (pinfunction "GPIO28/ADC2_42") (pintype "bidirectional"))
    )
    (net (code "87") (name "unconnected-(U1-GPIO29{slash}ADC3-Pad43)") (class "Default")
      (node (ref "U1") (pin "43") (pinfunction "GPIO29/ADC3_43") (pintype "bidirectional"))
    )
    (net (code "88") (name "unconnected-(U3-IO0-Pad12)") (class "Default")
      (node (ref "U3") (pin "12") (pinfunction "IO0_12") (pintype "bidirectional"))
    )
    (net (code "89") (name "unconnected-(U3-IO1-Pad13)") (class "Default")
      (node (ref "U3") (pin "13") (pinfunction "IO1_13") (pintype "bidirectional"))
    )
    (net (code "90") (name "unconnected-(U3-IO4-Pad18)") (class "Default")
      (node (ref "U3") (pin "18") (pinfunction "IO4_18") (pintype "bidirectional"))
    )
    (net (code "91") (name "unconnected-(U3-IO5-Pad19)") (class "Default")
      (node (ref "U3") (pin "19") (pinfunction "IO5_19") (pintype "bidirectional"))
    )
    (net (code "92") (name "unconnected-(U3-IO18-Pad26)") (class "Default")
      (node (ref "U3") (pin "26") (pinfunction "IO18_26") (pintype "bidirectional"))
    )
    (net (code "93") (name "unconnected-(U3-IO19-Pad27)") (class "Default")
      (node (ref "U3") (pin "27") (pinfunction "IO19_27") (pintype "bidirectional"))
    )
    (net (code "94") (name "unconnected-(U3-NC-Pad4)") (class "Default")
      (node (ref "U3") (pin "4") (pinfunction "NC_4") (pintype "no_connect"))
    )
    (net (code "95") (name "unconnected-(U3-NC-Pad7)") (class "Default")
      (node (ref "U3") (pin "7") (pinfunction "NC_7") (pintype "no_connect"))
    )
    (net (code "96") (name "unconnected-(U3-NC-Pad9)") (class "Default")
      (node (ref "U3") (pin "9") (pinfunction "NC_9") (pintype "no_connect"))
    )
    (net (code "97") (name "unconnected-(U3-NC-Pad10)") (class "Default")
      (node (ref "U3") (pin "10") (pinfunction "NC_10") (pintype "no_connect"))
    )
    (net (code "98") (name "unconnected-(U3-NC-Pad15)") (class "Default")
      (node (ref "U3") (pin "15") (pinfunction "NC_15") (pintype "no_connect"))
    )
    (net (code "99") (name "unconnected-(U3-NC-Pad17)") (class "Default")
      (node (ref "U3") (pin "17") (pinfunction "NC_17") (pintype "no_connect"))
    )
    (net (code "100") (name "unconnected-(U3-NC-Pad24)") (class "Default")
      (node (ref "U3") (pin "24") (pinfunction "NC_24") (pintype "no_connect"))
    )
    (net (code "101") (name "unconnected-(U3-NC-Pad25)") (class "Default")
      (node (ref "U3") (pin "25") (pinfunction "NC_25") (pintype "no_connect"))
    )
    (net (code "102") (name "unconnected-(U3-NC-Pad28)") (class "Default")
      (node (ref "U3") (pin "28") (pinfunction "NC_28") (pintype "no_connect"))
    )
    (net (code "103") (name "unconnected-(U3-NC-Pad29)") (class "Default")
      (node (ref "U3") (pin "29") (pinfunction "NC_29") (pintype "no_connect"))
    )
    (net (code "104") (name "unconnected-(U3-NC-Pad32)") (class "Default")
      (node (ref "U3") (pin "32") (pinfunction "NC_32") (pintype "no_connect"))
    )
    (net (code "105") (name "unconnected-(U3-NC-Pad33)") (class "Default")
      (node (ref "U3") (pin "33") (pinfunction "NC_33") (pintype "no_connect"))
    )
    (net (code "106") (name "unconnected-(U3-NC-Pad34)") (class "Default")
      (node (ref "U3") (pin "34") (pinfunction "NC_34") (pintype "no_connect"))
    )
    (net (code "107") (name "unconnected-(U3-NC-Pad35)") (class "Default")
      (node (ref "U3") (pin "35") (pinfunction "NC_35") (pintype "no_connect"))
    )
    (net (code "108") (name "unconnected-(U9-NC-Pad14)") (class "Default")
      (node (ref "U9") (pin "14") (pinfunction "NC_14") (pintype "no_connect"))
    )
    (net (code "109") (name "unconnected-(U10-CLKOUT-Pad7)") (class "Default")
      (node (ref "U10") (pin "7") (pinfunction "CLKOUT_7") (pintype "output"))
    )
    (net (code "110") (name "unconnected-(U14-DO-PadP$2)") (class "Default")
      (node (ref "U14") (pin "P$2") (pinfunction "DO_P$2") (pintype "bidirectional"))
    )
    (net (code "111") (name "~{ESP32_BOOT}") (class "Default")
      (node (ref "U1") (pin "31") (pinfunction "GPIO19_31") (pintype "bidirectional"))
      (node (ref "U3") (pin "23") (pinfunction "IO9_23") (pintype "bidirectional"))
    )
    (net (code "112") (name "~{ESP32_RST}") (class "Default")
      (node (ref "U1") (pin "29") (pinfunction "GPIO18_29") (pintype "bidirectional"))
      (node (ref "U3") (pin "8") (pinfunction "EN_8") (pintype "input"))
    )
    (net (code "113") (name "~{FLASH_CS}") (class "Default")
      (node (ref "R7") (pin "2") (pinfunction "2_2") (pintype "passive"))
      (node (ref "U1") (pin "2") (pinfunction "GPIO0_2") (pintype "bidirectional"))
      (node (ref "U2") (pin "1") (pinfunction "~{CE}_1") (pintype "bidirectional"))
    )
    (net (code "114") (name "~{QSPI_CS}") (class "Default")
      (node (ref "IC1") (pin "1") (pinfunction "~{CS}_1") (pintype "bidirectional"))
      (node (ref "R5") (pin "1") (pinfunction "1_1") (pintype "passive"))
      (node (ref "R6") (pin "2") (pinfunction "2_2") (pintype "passive"))
      (node (ref "U1") (pin "60") (pinfunction "QSPI_~{CS}_60") (pintype "bidirectional"))
    )
    (net (code "115") (name "~{RESET}") (class "Default")
      (node (ref "RESET") (pin "1") (pinfunction "1_1") (pintype "passive"))
      (node (ref "RESET") (pin "2") (pinfunction "1_2") (pintype "passive"))
      (node (ref "U1") (pin "26") (pinfunction "RUN_26") (pintype "bidirectional"))
    )
    (net (code "116") (name "~{USB_BOOT}") (class "Default")
      (node (ref "!BOOT") (pin "3") (pinfunction "2_3") (pintype "passive"))
      (node (ref "!BOOT") (pin "4") (pinfunction "2_4") (pintype "passive"))
      (node (ref "R6") (pin "1") (pinfunction "1_1") (pintype "passive"))
    )
  )
)
